# Apollo_Main_Board.net
KiCad netlist of a schematic drawn in Altium Designer
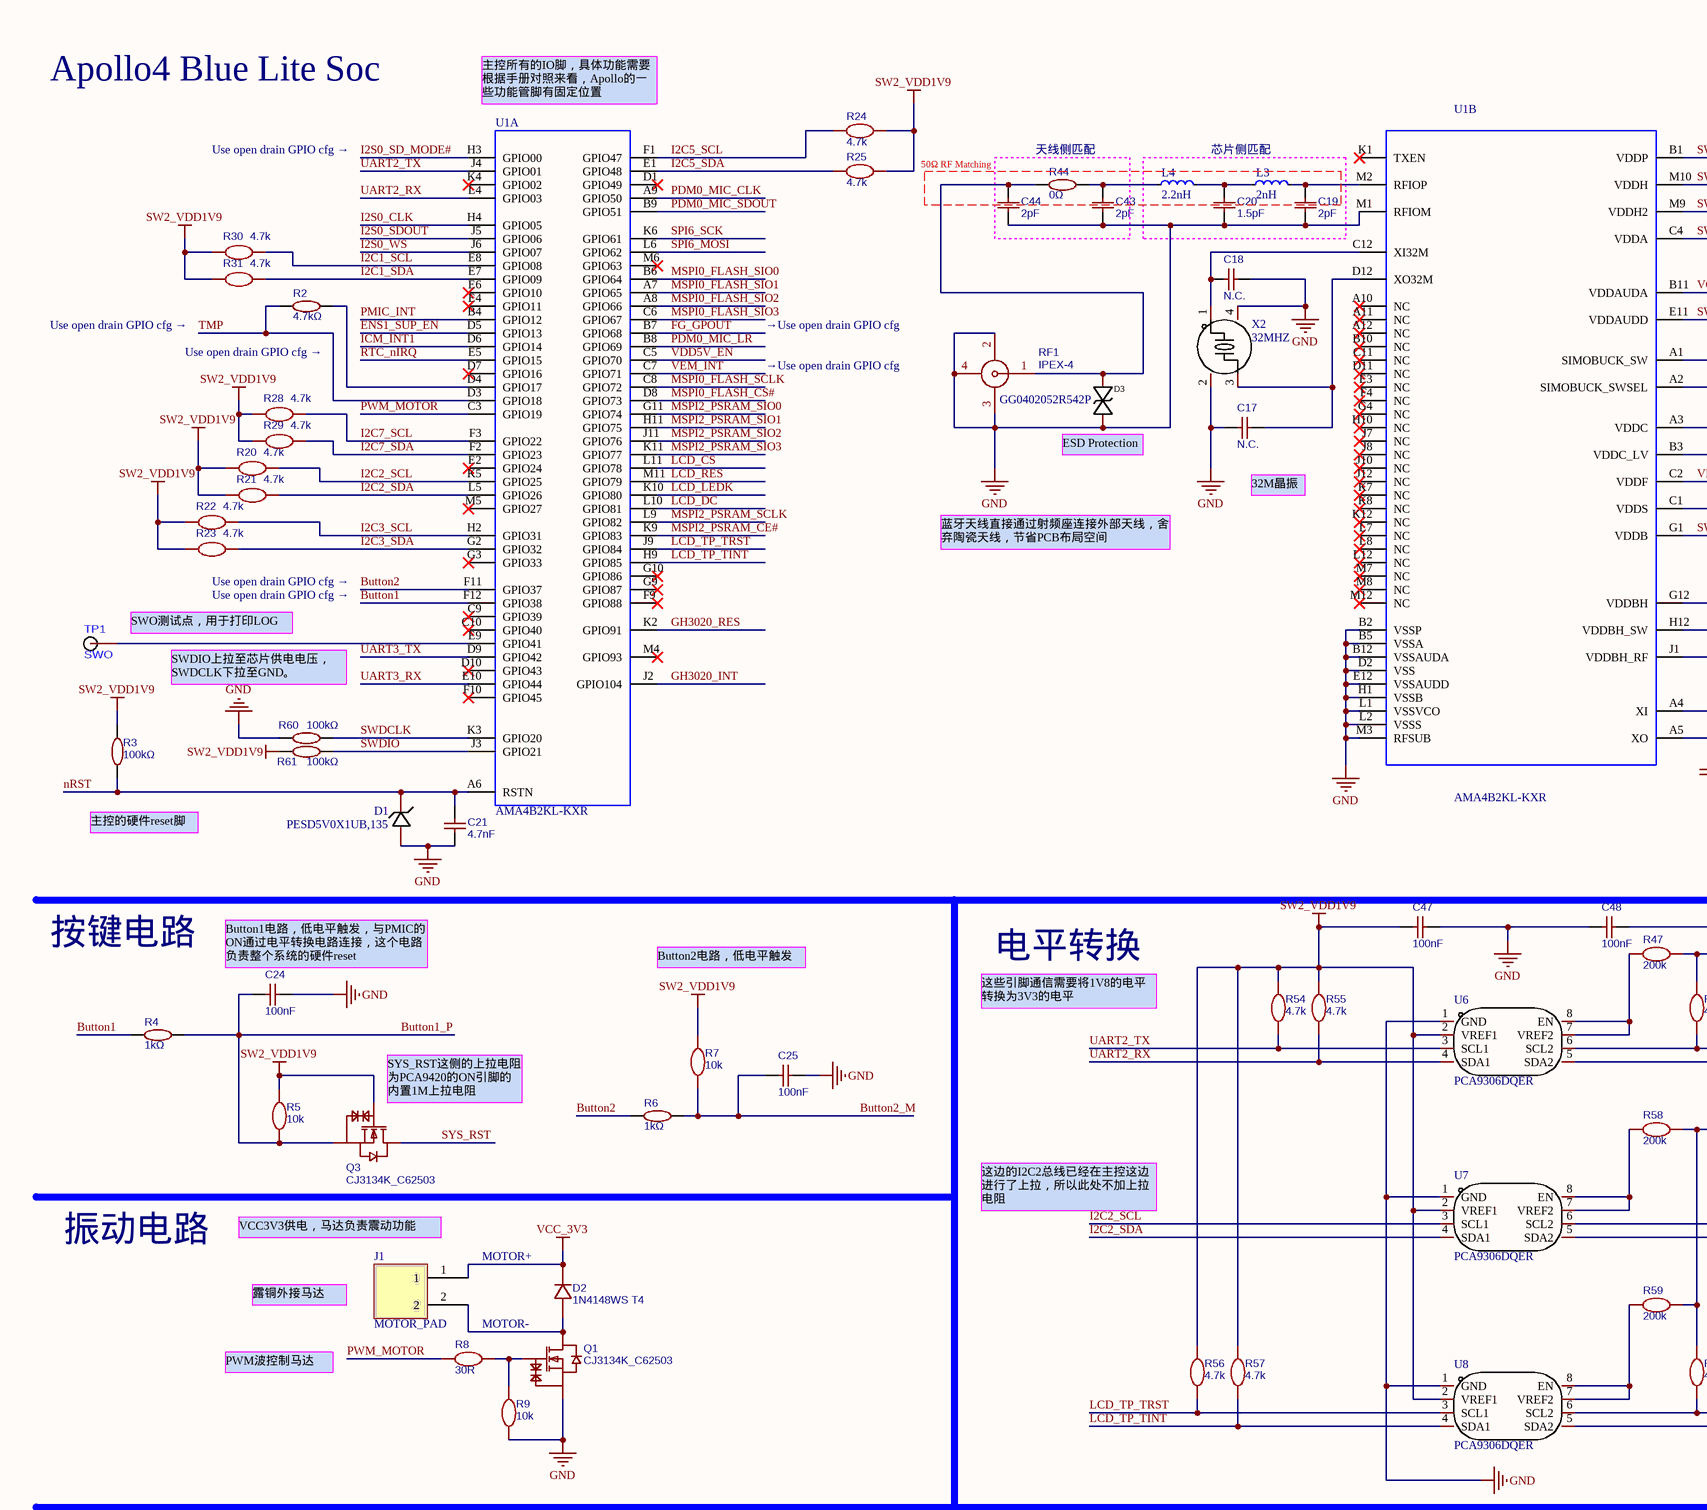
[diagram p0: Apollo_Main_Board.SchDoc, top left]
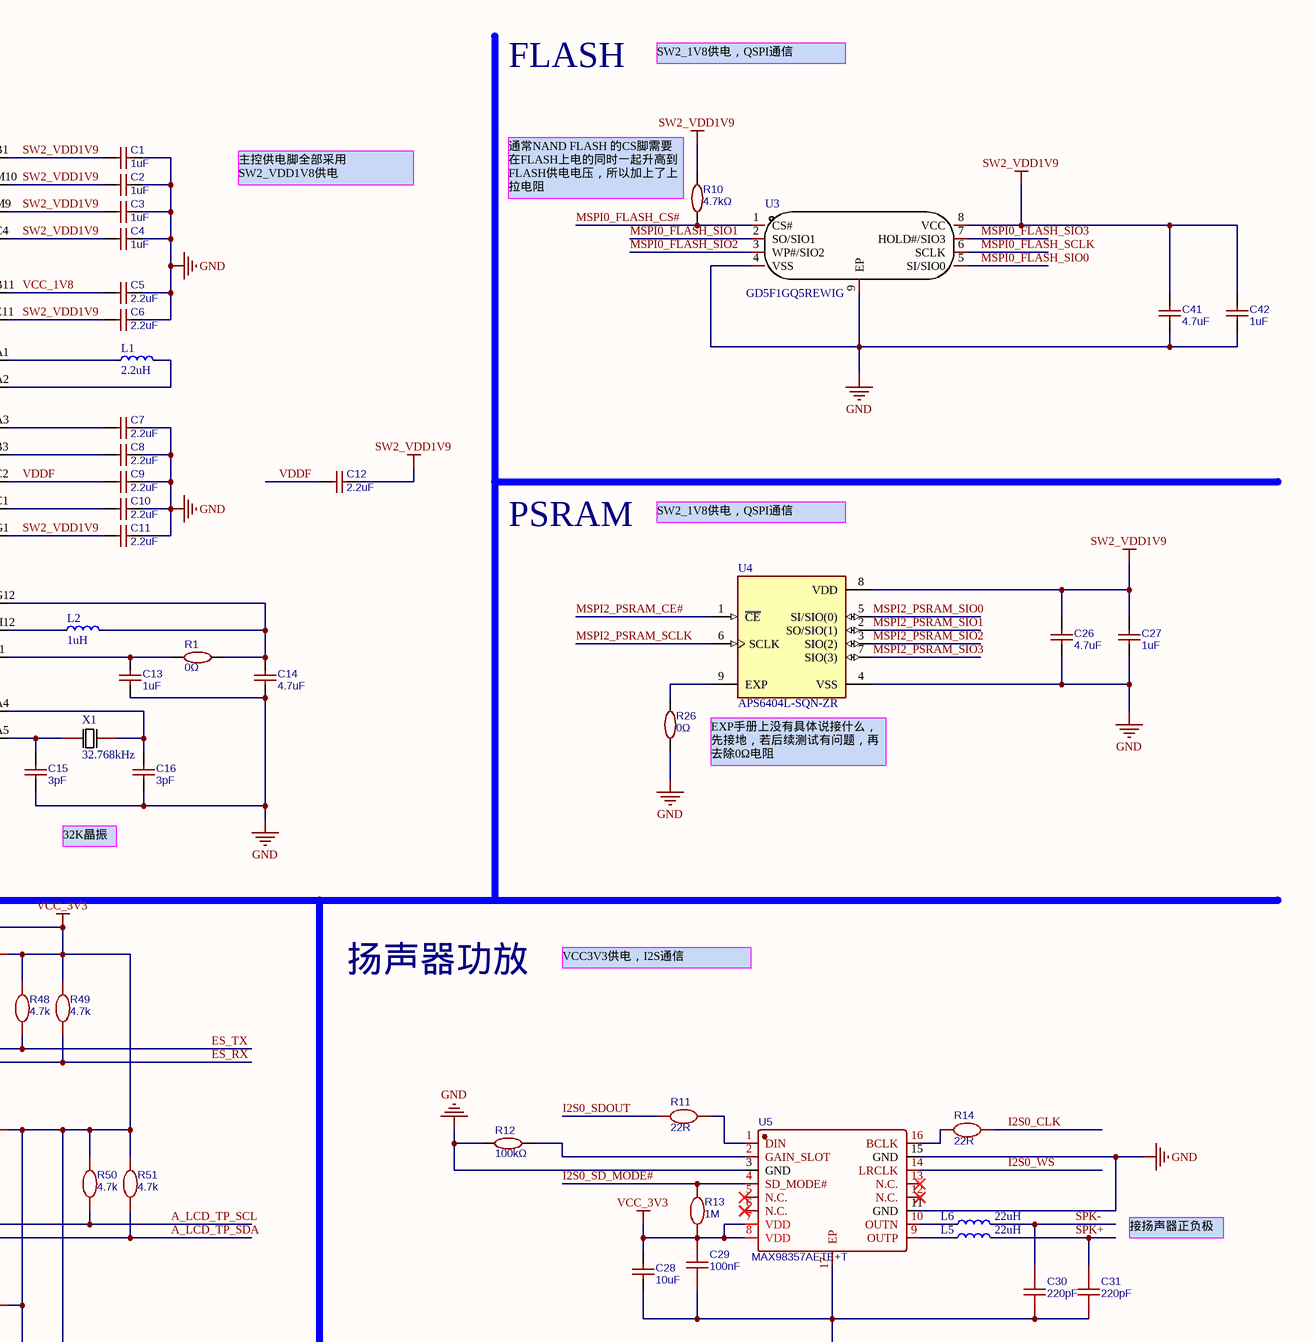
[diagram p1: Apollo_Main_Board.SchDoc, top right]
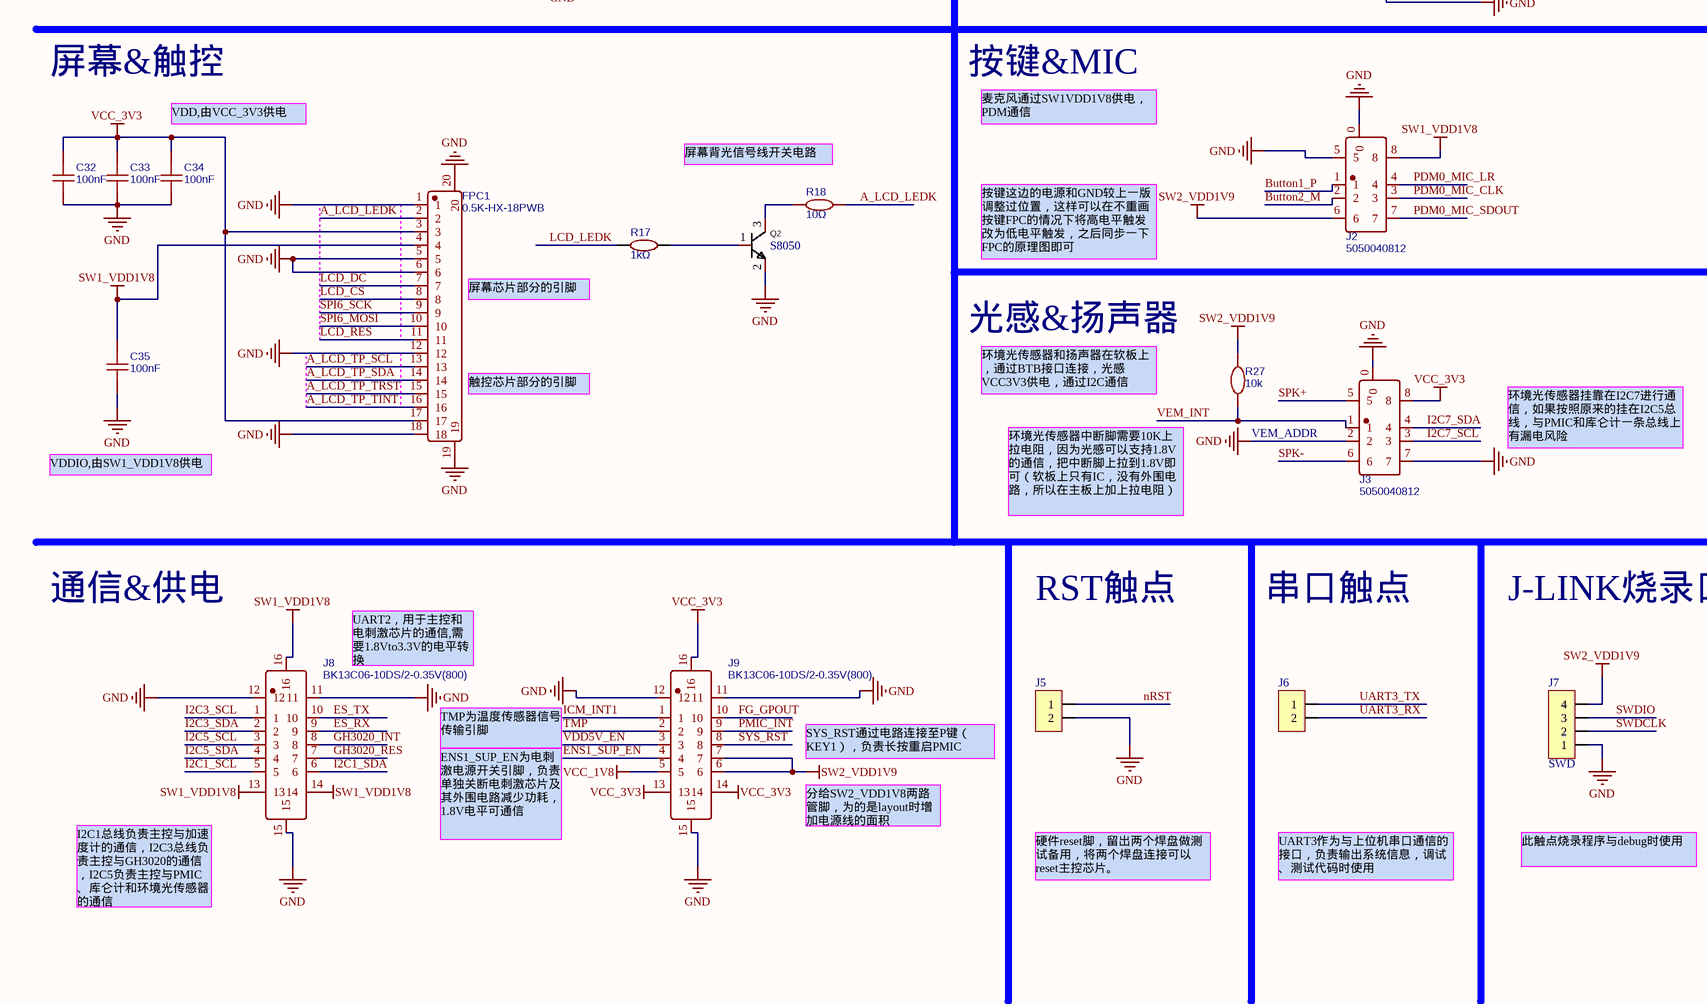
[diagram p2: Apollo_Main_Board.SchDoc, bottom left]
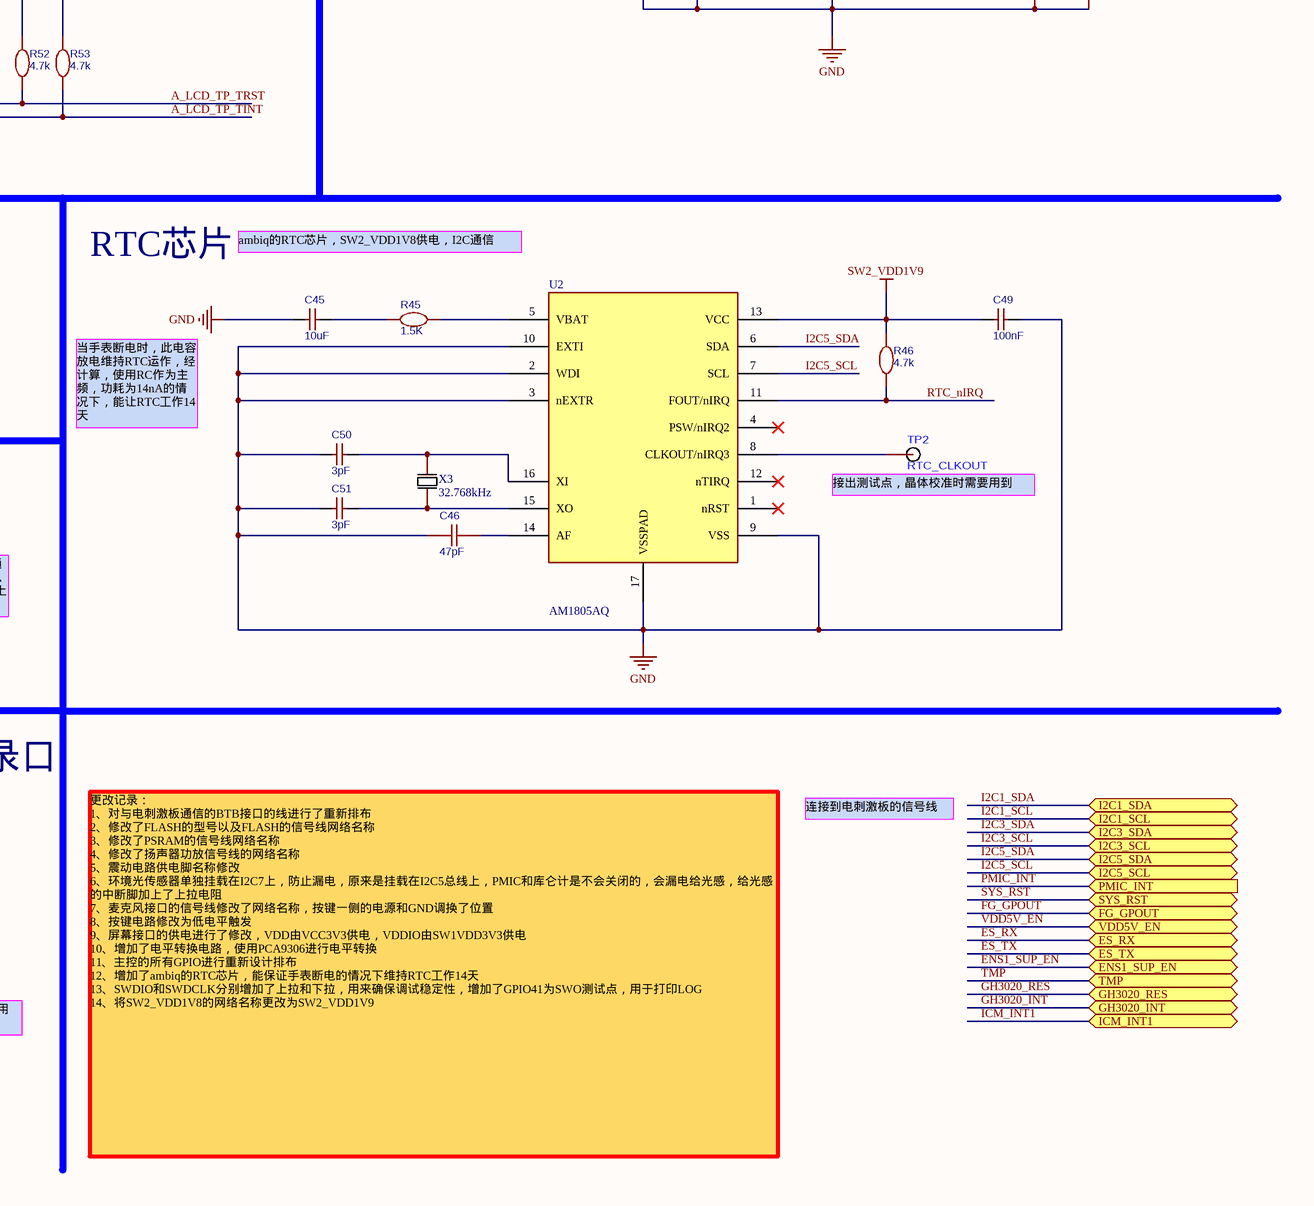
[diagram p3: Apollo_Main_Board.SchDoc, bottom right]

(export (version "E")
  (design (tool "Eeschema 10.0.6"))
  (components
    (comp (ref "C1")
      (value "1uF")
      (footprint "C0201")
      (description "GRM033R61A105ME44D\r\n精度: ±20%\r\n额定电压: 10V\r\n材质(温度系数): X5R")
      (fields
        (field (name "BOM_MANUFACTURER PART") "CL10A105KB8NNNC")
        (field (name "BOM_SUPPLIER PART") "C15849")
      )
      (libsource (lib "smart bracelet") (part "1uF"))
    )
    (comp (ref "C2")
      (value "1uF")
      (footprint "C0201")
      (description "GRM033R61A105ME44D\r\n精度: ±20%\r\n额定电压: 10V\r\n材质(温度系数): X5R")
      (fields
        (field (name "BOM_MANUFACTURER PART") "CL10A105KB8NNNC")
        (field (name "BOM_SUPPLIER PART") "C15849")
      )
      (libsource (lib "smart bracelet") (part "1uF"))
    )
    (comp (ref "C3")
      (value "1uF")
      (footprint "C0201")
      (description "GRM033R61A105ME44D\r\n精度: ±20%\r\n额定电压: 10V\r\n材质(温度系数): X5R")
      (fields
        (field (name "BOM_MANUFACTURER PART") "CL10A105KB8NNNC")
        (field (name "BOM_SUPPLIER PART") "C15849")
      )
      (libsource (lib "smart bracelet") (part "1uF"))
    )
    (comp (ref "C4")
      (value "1uF")
      (footprint "C0201")
      (description "GRM033R61A105ME44D\r\n精度: ±20%\r\n额定电压: 10V\r\n材质(温度系数): X5R")
      (fields
        (field (name "BOM_MANUFACTURER PART") "CL10A105KB8NNNC")
        (field (name "BOM_SUPPLIER PART") "C15849")
      )
      (libsource (lib "smart bracelet") (part "1uF"))
    )
    (comp (ref "C5")
      (value "2.2uF")
      (footprint "C0201")
      (description "GRM033R61A225KE47D\r\n精度: ±10%\r\n额定电压: 10V\r\n材质(温度系数): X5R")
      (fields
        (field (name "BOM_MANUFACTURER PART") "CL10A105KB8NNNC")
        (field (name "BOM_SUPPLIER PART") "C15849")
      )
      (libsource (lib "smart bracelet") (part "1uF"))
    )
    (comp (ref "C6")
      (value "2.2uF")
      (footprint "C0201")
      (description "GRM033R61A225KE47D\r\n精度: ±10%\r\n额定电压: 10V\r\n材质(温度系数): X5R")
      (fields
        (field (name "BOM_MANUFACTURER PART") "CL10A105KB8NNNC")
        (field (name "BOM_SUPPLIER PART") "C15849")
      )
      (libsource (lib "smart bracelet") (part "1uF"))
    )
    (comp (ref "C7")
      (value "2.2uF")
      (footprint "C0201")
      (description "GRM033R61A225KE47D\r\n精度: ±10%\r\n额定电压: 10V\r\n材质(温度系数): X5R")
      (fields
        (field (name "BOM_MANUFACTURER PART") "CL10A105KB8NNNC")
        (field (name "BOM_SUPPLIER PART") "C15849")
      )
      (libsource (lib "smart bracelet") (part "1uF"))
    )
    (comp (ref "C8")
      (value "2.2uF")
      (footprint "C0201")
      (description "GRM033R61A225KE47D\r\n精度: ±10%\r\n额定电压: 10V\r\n材质(温度系数): X5R")
      (fields
        (field (name "BOM_MANUFACTURER PART") "CL10A105KB8NNNC")
        (field (name "BOM_SUPPLIER PART") "C15849")
      )
      (libsource (lib "smart bracelet") (part "1uF"))
    )
    (comp (ref "C9")
      (value "2.2uF")
      (footprint "C0201")
      (description "GRM033R61A225KE47D\r\n精度: ±10%\r\n额定电压: 10V\r\n材质(温度系数): X5R")
      (fields
        (field (name "BOM_MANUFACTURER PART") "CL10A105KB8NNNC")
        (field (name "BOM_SUPPLIER PART") "C15849")
      )
      (libsource (lib "smart bracelet") (part "1uF"))
    )
    (comp (ref "C10")
      (value "2.2uF")
      (footprint "C0201")
      (description "GRM033R61A225KE47D\r\n精度: ±10%\r\n额定电压: 10V\r\n材质(温度系数): X5R")
      (fields
        (field (name "BOM_MANUFACTURER PART") "CL10A105KB8NNNC")
        (field (name "BOM_SUPPLIER PART") "C15849")
      )
      (libsource (lib "smart bracelet") (part "1uF"))
    )
    (comp (ref "C11")
      (value "2.2uF")
      (footprint "C0201")
      (description "GRM033R61A225KE47D\r\n精度: ±10%\r\n额定电压: 10V\r\n材质(温度系数): X5R")
      (fields
        (field (name "BOM_MANUFACTURER PART") "CL10A105KB8NNNC")
        (field (name "BOM_SUPPLIER PART") "C15849")
      )
      (libsource (lib "smart bracelet") (part "1uF"))
    )
    (comp (ref "C12")
      (value "2.2uF")
      (footprint "C0201")
      (description "GRM033R61A225KE47D\r\n精度: ±10%\r\n额定电压: 10V\r\n材质(温度系数): X5R")
      (fields
        (field (name "BOM_MANUFACTURER PART") "CL10A105KB8NNNC")
        (field (name "BOM_SUPPLIER PART") "C15849")
      )
      (libsource (lib "smart bracelet") (part "1uF"))
    )
    (comp (ref "C13")
      (value "1uF")
      (footprint "C0201")
      (description "GRM033R61A105ME44D\r\n精度: ±20%\r\n额定电压: 10V\r\n材质(温度系数): X5R")
      (fields
        (field (name "BOM_MANUFACTURER PART") "CL10A105KB8NNNC")
        (field (name "BOM_SUPPLIER PART") "C15849")
      )
      (libsource (lib "smart bracelet") (part "1uF"))
    )
    (comp (ref "C14")
      (value "4.7uF")
      (footprint "C0201")
      (description "GRM035R60J475ME15D\r\n精度: ±20%\r\n额定电压: 6.3V\r\n材质(温度系数): X5R")
      (fields
        (field (name "BOM_MANUFACTURER PART") "CL10A105KB8NNNC")
        (field (name "BOM_SUPPLIER PART") "C15849")
      )
      (libsource (lib "smart bracelet") (part "1uF"))
    )
    (comp (ref "C15")
      (value "3pF")
      (footprint "C0201")
      (fields
        (field (name "BOM_MANUFACTURER PART") "CL10A105KB8NNNC")
        (field (name "BOM_SUPPLIER PART") "C15849")
      )
      (libsource (lib "smart bracelet") (part "1uF"))
    )
    (comp (ref "C16")
      (value "3pF")
      (footprint "C0201")
      (fields
        (field (name "BOM_MANUFACTURER PART") "CL10A105KB8NNNC")
        (field (name "BOM_SUPPLIER PART") "C15849")
      )
      (libsource (lib "smart bracelet") (part "1uF"))
    )
    (comp (ref "C17")
      (value "N.C.")
      (footprint "C0201")
      (description "现在选的32MHZ晶振内部负载电容8pF，可以不需要外部电容，所以NC，只留焊盘，不用焊接")
      (fields
        (field (name "BOM_MANUFACTURER PART") "CL10A105KB8NNNC")
        (field (name "BOM_SUPPLIER PART") "C15849")
      )
      (libsource (lib "smart bracelet") (part "1uF"))
    )
    (comp (ref "C18")
      (value "N.C.")
      (footprint "C0201")
      (description "现在选的32MHZ晶振内部负载电容8pF，可以不需要外部电容，所以NC，只留焊盘，不用焊接")
      (fields
        (field (name "BOM_MANUFACTURER PART") "CL10A105KB8NNNC")
        (field (name "BOM_SUPPLIER PART") "C15849")
      )
      (libsource (lib "smart bracelet") (part "1uF"))
    )
    (comp (ref "C19")
      (value "2pF")
      (footprint "C0201")
      (description "GRM0335C1H2R0BA01D\r\n精度: ±0.1pF\r\n额定电压: 50V\r\n材质(温度系数): C0G")
      (fields
        (field (name "BOM_MANUFACTURER PART") "CL10A105KB8NNNC")
        (field (name "BOM_SUPPLIER PART") "C15849")
      )
      (libsource (lib "smart bracelet") (part "1uF"))
    )
    (comp (ref "C20")
      (value "1.5pF")
      (footprint "C0201")
      (description "GRM0335C1H1R5BA01D\r\n精度: ±0.1pF\r\n额定电压: 50V\r\n材质(温度系数): C0G")
      (fields
        (field (name "BOM_MANUFACTURER PART") "CL10A105KB8NNNC")
        (field (name "BOM_SUPPLIER PART") "C15849")
      )
      (libsource (lib "smart bracelet") (part "1uF"))
    )
    (comp (ref "C21")
      (value "4.7nF")
      (footprint "C0201")
      (description "CC0201KRX7R8BB472\r\n精度: ±10%\r\n额定电压: 25V\r\n材质(温度系数): X7R")
      (fields
        (field (name "BOM_MANUFACTURER PART") "CL10A105KB8NNNC")
        (field (name "BOM_SUPPLIER PART") "C15849")
      )
      (libsource (lib "smart bracelet") (part "1uF"))
    )
    (comp (ref "C24")
      (value "100nF")
      (footprint "C0201")
      (description "CL03A104KO3NNNC\r\n精度: ±10%\r\n额定电压: 16V\r\n材质(温度系数): X5R")
      (fields
        (field (name "BOM_MANUFACTURER PART") "CL10A105KB8NNNC")
        (field (name "BOM_SUPPLIER PART") "C15849")
      )
      (libsource (lib "smart bracelet") (part "1uF"))
    )
    (comp (ref "C25")
      (value "100nF")
      (footprint "C0201")
      (description "CL03A104KO3NNNC\r\n精度: ±10%\r\n额定电压: 16V\r\n材质(温度系数): X5R")
      (fields
        (field (name "BOM_MANUFACTURER PART") "CL10A105KB8NNNC")
        (field (name "BOM_SUPPLIER PART") "C15849")
      )
      (libsource (lib "smart bracelet") (part "1uF"))
    )
    (comp (ref "C26")
      (value "4.7uF")
      (footprint "C0201")
      (description "GRM035R60J475ME15D\r\n精度: ±20%\r\n额定电压: 6.3V\r\n材质(温度系数): X5R")
      (fields
        (field (name "BOM_MANUFACTURER PART") "CL10A105KB8NNNC")
        (field (name "BOM_SUPPLIER PART") "C15849")
      )
      (libsource (lib "smart bracelet") (part "1uF"))
    )
    (comp (ref "C27")
      (value "1uF")
      (footprint "C0201")
      (description "GRM033R61A105ME44D\r\n精度: ±20%\r\n额定电压: 10V\r\n材质(温度系数): X5R")
      (fields
        (field (name "BOM_MANUFACTURER PART") "CL10A105KB8NNNC")
        (field (name "BOM_SUPPLIER PART") "C15849")
      )
      (libsource (lib "smart bracelet") (part "1uF"))
    )
    (comp (ref "C28")
      (value "10uF")
      (footprint "C0402")
      (description "GRM155R61A106ME11D\r\n精度: ±20%\r\n额定电压: 10V\r\n材质(温度系数): X5R")
      (fields
        (field (name "BOM_MANUFACTURER PART") "CL10A105KB8NNNC")
        (field (name "BOM_SUPPLIER PART") "C15849")
      )
      (libsource (lib "smart bracelet") (part "1uF"))
    )
    (comp (ref "C29")
      (value "100nF")
      (footprint "smart bracelet:C0201")
      (description "CL03A104KO3NNNC\r\n额定电压: 16V\r\n材质(温度系数): X5R")
      (fields
        (field (name "BOM_MANUFACTURER PART") "CL10B104KB8NNNC")
        (field (name "BOM_SUPPLIER PART") "C1591")
      )
      (libsource (lib "smart bracelet") (part "100nF"))
    )
    (comp (ref "C30")
      (value "220pF")
      (footprint "smart bracelet:C0201")
      (description "GRM0335C1H221JA01D\r\n精度: ±5%\r\n额定电压: 50V\r\n材质(温度系数): C0G")
      (fields
        (field (name "BOM_SUPPLIER PART") "C913904")
        (field (name "BOM_MANUFACTURER PART") "CL10A225KB8NNNC")
        (field (name "CONTRIBUTOR") "LCSC")
      )
      (libsource (lib "smart bracelet") (part "C0201"))
    )
    (comp (ref "C31")
      (value "220pF")
      (footprint "smart bracelet:C0201")
      (description "GRM0335C1H221JA01D\r\n精度: ±5%\r\n额定电压: 50V\r\n材质(温度系数): C0G")
      (fields
        (field (name "BOM_SUPPLIER PART") "C913904")
        (field (name "BOM_MANUFACTURER PART") "CL10A225KB8NNNC")
        (field (name "CONTRIBUTOR") "LCSC")
      )
      (libsource (lib "smart bracelet") (part "C0201"))
    )
    (comp (ref "C32")
      (value "100nF")
      (footprint "smart bracelet:C0201")
      (description "CL03A104KO3NNNC\r\n额定电压: 16V\r\n材质(温度系数): X5R")
      (fields
        (field (name "BOM_MANUFACTURER PART") "CL10B104KB8NNNC")
        (field (name "BOM_SUPPLIER PART") "C1591")
      )
      (libsource (lib "smart bracelet") (part "100nF"))
    )
    (comp (ref "C33")
      (value "100nF")
      (footprint "smart bracelet:C0201")
      (description "CL03A104KO3NNNC\r\n额定电压: 16V\r\n材质(温度系数): X5R")
      (fields
        (field (name "BOM_MANUFACTURER PART") "CL10B104KB8NNNC")
        (field (name "BOM_SUPPLIER PART") "C1591")
      )
      (libsource (lib "smart bracelet") (part "100nF"))
    )
    (comp (ref "C34")
      (value "100nF")
      (footprint "smart bracelet:C0201")
      (description "CL03A104KO3NNNC\r\n额定电压: 16V\r\n材质(温度系数): X5R")
      (fields
        (field (name "BOM_MANUFACTURER PART") "CL10B104KB8NNNC")
        (field (name "BOM_SUPPLIER PART") "C1591")
      )
      (libsource (lib "smart bracelet") (part "100nF"))
    )
    (comp (ref "C35")
      (value "100nF")
      (footprint "smart bracelet:C0201")
      (description "CL03A104KO3NNNC\r\n额定电压: 16V\r\n材质(温度系数): X5R")
      (fields
        (field (name "BOM_MANUFACTURER PART") "CL10B104KB8NNNC")
        (field (name "BOM_SUPPLIER PART") "C1591")
      )
      (libsource (lib "smart bracelet") (part "100nF"))
    )
    (comp (ref "C41")
      (value "4.7uF")
      (footprint "C0201")
      (description "GRM035R60J475ME15D\r\n精度: ±20%\r\n额定电压: 6.3V\r\n材质(温度系数): X5R")
      (fields
        (field (name "BOM_MANUFACTURER PART") "CL10A105KB8NNNC")
        (field (name "BOM_SUPPLIER PART") "C15849")
      )
      (libsource (lib "smart bracelet") (part "1uF"))
    )
    (comp (ref "C42")
      (value "1uF")
      (footprint "C0201")
      (description "GRM033R61A105ME44D\r\n精度: ±20%\r\n额定电压: 10V\r\n材质(温度系数): X5R")
      (fields
        (field (name "BOM_MANUFACTURER PART") "CL10A105KB8NNNC")
        (field (name "BOM_SUPPLIER PART") "C15849")
      )
      (libsource (lib "smart bracelet") (part "1uF"))
    )
    (comp (ref "C43")
      (value "2pF")
      (footprint "C0201")
      (description "GRM0335C1H2R0BA01D\r\n精度: ±0.1pF\r\n额定电压: 50V\r\n材质(温度系数): C0G")
      (fields
        (field (name "BOM_MANUFACTURER PART") "CL10A105KB8NNNC")
        (field (name "BOM_SUPPLIER PART") "C15849")
      )
      (libsource (lib "smart bracelet") (part "1uF"))
    )
    (comp (ref "C44")
      (value "2pF")
      (footprint "C0201")
      (description "GRM0335C1H2R0BA01D\r\n精度: ±0.1pF\r\n额定电压: 50V\r\n材质(温度系数): C0G")
      (fields
        (field (name "BOM_MANUFACTURER PART") "CL10A105KB8NNNC")
        (field (name "BOM_SUPPLIER PART") "C15849")
      )
      (libsource (lib "smart bracelet") (part "1uF"))
    )
    (comp (ref "C45")
      (value "10uF")
      (footprint "C0402")
      (description "GRM155R61A106ME11D\r\n精度: ±20%\r\n额定电压: 10V\r\n材质(温度系数): X5R")
      (fields
        (field (name "BOM_MANUFACTURER PART") "CL10A105KB8NNNC")
        (field (name "BOM_SUPPLIER PART") "C15849")
      )
      (libsource (lib "smart bracelet") (part "1uF"))
    )
    (comp (ref "C46")
      (value "47pF")
      (footprint "smart bracelet:C0201")
      (fields
        (field (name "BOM_SUPPLIER PART") "C913904")
        (field (name "BOM_MANUFACTURER PART") "CL10A225KB8NNNC")
        (field (name "CONTRIBUTOR") "LCSC")
      )
      (libsource (lib "smart bracelet") (part "C0201"))
    )
    (comp (ref "C47")
      (value "100nF")
      (footprint "C0201")
      (description "CL03A104KO3NNNC\r\n精度: ±10%\r\n额定电压: 16V\r\n材质(温度系数): X5R")
      (fields
        (field (name "BOM_MANUFACTURER PART") "CL10A105KB8NNNC")
        (field (name "BOM_SUPPLIER PART") "C15849")
      )
      (libsource (lib "smart bracelet") (part "1uF"))
    )
    (comp (ref "C48")
      (value "100nF")
      (footprint "C0201")
      (description "CL03A104KO3NNNC\r\n精度: ±10%\r\n额定电压: 16V\r\n材质(温度系数): X5R")
      (fields
        (field (name "BOM_MANUFACTURER PART") "CL10A105KB8NNNC")
        (field (name "BOM_SUPPLIER PART") "C15849")
      )
      (libsource (lib "smart bracelet") (part "1uF"))
    )
    (comp (ref "C49")
      (value "100nF")
      (footprint "C0201")
      (description "CL03A104KO3NNNC\r\n精度: ±10%\r\n额定电压: 16V\r\n材质(温度系数): X5R")
      (fields
        (field (name "BOM_MANUFACTURER PART") "CL10A105KB8NNNC")
        (field (name "BOM_SUPPLIER PART") "C15849")
      )
      (libsource (lib "smart bracelet") (part "1uF"))
    )
    (comp (ref "C50")
      (value "3pF")
      (footprint "C0201")
      (fields
        (field (name "BOM_MANUFACTURER PART") "CL10A105KB8NNNC")
        (field (name "BOM_SUPPLIER PART") "C15849")
      )
      (libsource (lib "smart bracelet") (part "1uF"))
    )
    (comp (ref "C51")
      (value "3pF")
      (footprint "C0201")
      (fields
        (field (name "BOM_MANUFACTURER PART") "CL10A105KB8NNNC")
        (field (name "BOM_SUPPLIER PART") "C15849")
      )
      (libsource (lib "smart bracelet") (part "1uF"))
    )
    (comp (ref "D1")
      (value "PESD5V0X1UB,135")
      (footprint "SOD-523_L1.2-W0.8-LS1.6-RD")
      (fields (field (name "MANUFACTURER") "Nexperia(安世)") (field (name "NAME") "PESD5V0X1UB,135"))
      (libsource (lib "smart bracelet") (part "PESD5V0X1UB,135"))
    )
    (comp (ref "D2")
      (value "1N4148WS T4")
      (footprint "smart bracelet:SOD-323_L1.8-W1.3-LS2.5-RD")
      (fields (field (name "MANUFACTURER") "CJ(江苏长电/长晶)") (field (name "MANUFACTURER PART") "1N4148WS"))
      (libsource (lib "smart bracelet") (part "1N4148WS T4"))
    )
    (comp (ref "D3")
      (value "GG0402052R542P")
      (footprint "smart bracelet:0402")
      (fields (field (name "MANUFACTURER") "Kyocera AVX"))
      (libsource (lib "smart bracelet") (part "GG0402052R542P"))
    )
    (comp (ref "FPC1")
      (value "0.5K-HX-18PWB")
      (footprint "smart bracelet:FPC-SMD_18P-P0.50_HDGC_0.5K-HX-18PWB")
      (fields (field (name "BOM_SUPPLIER PART") "C2919497") (field (name "CONTRIBUTOR") "LCSC"))
      (libsource (lib "smart bracelet") (part "0.5K-HX-18PWB"))
    )
    (comp (ref "J1")
      (value "MOTOR_PAD")
      (footprint "smart bracelet:MOTOR_PAD")
      (libsource (lib "smart bracelet") (part "MOTOR_PAD"))
    )
    (comp (ref "J2")
      (value "5050040812")
      (footprint "smart bracelet:CONN-SMD_4P-P0.40_5050040812")
      (fields (field (name "MANUFACTURER") "MOLEX") (field (name "CONTRIBUTOR") "lcsc"))
      (libsource (lib "smart bracelet") (part "5050040812_8pin_ds"))
    )
    (comp (ref "J3")
      (value "5050040812")
      (footprint "smart bracelet:CONN-SMD_4P-P0.40_5050040812")
      (fields (field (name "MANUFACTURER") "MOLEX") (field (name "CONTRIBUTOR") "lcsc"))
      (libsource (lib "smart bracelet") (part "5050040812_8pin_ds"))
    )
    (comp (ref "J5")
      (value "~")
      (footprint "2PIN_1.27mm")
      (description "Header, 2-Pin, encryption interface")
      (fields (field (name "PUBLISHER") "Altium Limited"))
      (libsource (lib "smart bracelet") (part "Header 2"))
    )
    (comp (ref "J6")
      (value "~")
      (footprint "2PIN_1.27mm")
      (description "Header, 2-Pin, encryption interface")
      (fields (field (name "PUBLISHER") "Altium Limited"))
      (libsource (lib "smart bracelet") (part "Header 2"))
    )
    (comp (ref "J7")
      (value "SWD")
      (footprint "4PIN_1.27mm")
      (description "Header, 4-Pin")
      (fields (field (name "PUBLISHER") "Altium Limited"))
      (libsource (lib "smart bracelet") (part "Header 4"))
    )
    (comp (ref "J8")
      (value "BK13C06-10DS/2-0.35V(800)")
      (footprint "smart bracelet:CONN-SMD_BK13C06-10DS-2-0.35V-800")
      (fields (field (name "MANUFACTURER") "HRS(广濑)") (field (name "CONTRIBUTOR") "lcsc"))
      (libsource (lib "smart bracelet") (part "10pin_ds_BK13C06-10DS/2-0.35V(800)"))
    )
    (comp (ref "J9")
      (value "BK13C06-10DS/2-0.35V(800)")
      (footprint "smart bracelet:CONN-SMD_BK13C06-10DS-2-0.35V-800")
      (fields (field (name "MANUFACTURER") "HRS(广濑)") (field (name "CONTRIBUTOR") "lcsc"))
      (libsource (lib "smart bracelet") (part "10pin_ds_BK13C06-10DS/2-0.35V(800)"))
    )
    (comp (ref "L1")
      (value "2.2uH")
      (footprint "C0603")
      (description "MAP1608ST2R2MMPK（这是按照官方推荐的选型，不要轻易变动）")
      (fields (field (name "PART NUMBER") "L0603-10µ"))
      (libsource (lib "smart bracelet") (part "10uH"))
    )
    (comp (ref "L2")
      (value "1uH")
      (footprint "C0603")
      (description "MAP1608ST1R0MMPK（这是按照官方推荐的选型，不要轻易变动）")
      (fields (field (name "PART NUMBER") "L0603-10µ"))
      (libsource (lib "smart bracelet") (part "10uH"))
    )
    (comp (ref "L3")
      (value "2nH")
      (footprint "C0201")
      (fields (field (name "PART NUMBER") "L0603-10µ"))
      (libsource (lib "smart bracelet") (part "10uH"))
    )
    (comp (ref "L4")
      (value "2.2nH")
      (footprint "C0201")
      (fields (field (name "PART NUMBER") "L0603-10µ"))
      (libsource (lib "smart bracelet") (part "10uH"))
    )
    (comp (ref "L5")
      (value "22uH")
      (footprint "0603A")
      (fields (field (name "PART NUMBER") "L0603-10µ"))
      (libsource (lib "smart bracelet") (part "10uH"))
    )
    (comp (ref "L6")
      (value "22uH")
      (footprint "0603A")
      (fields (field (name "PART NUMBER") "L0603-10µ"))
      (libsource (lib "smart bracelet") (part "10uH"))
    )
    (comp (ref "Q1")
      (value "CJ3134K_C62503")
      (footprint "smart bracelet:SOT-723_L1.2-W0.8-P0.40-LS1.2-BR")
      (fields (field (name "MANUFACTURER") "CJ(江苏长电/长晶)") (field (name "MANUFACTURER PART") "CJ3134K KF"))
      (libsource (lib "smart bracelet") (part "CJ3134K_C62503"))
    )
    (comp (ref "Q2")
      (value "S8050")
      (footprint "smart bracelet:SOT-23")
      (fields (field (name "MANUFACTURER") "星海"))
      (libsource (lib "smart bracelet") (part "S8050"))
    )
    (comp (ref "Q3")
      (value "CJ3134K_C62503")
      (footprint "smart bracelet:SOT-723_L1.2-W0.8-P0.40-LS1.2-BR")
      (fields (field (name "MANUFACTURER") "CJ(江苏长电/长晶)") (field (name "MANUFACTURER PART") "CJ3134K KF"))
      (libsource (lib "smart bracelet") (part "CJ3134K_C62503"))
    )
    (comp (ref "R1")
      (value "0Ω")
      (footprint "smart bracelet:RES0201")
      (description "RC0201FR-070RL\r\n品牌: YAGEO(国巨)\r\n封装: 0201\r\n电阻类型: 厚膜电阻\r\n阻值: 0Ω\r\n精度: ±1%\r\n功率: 50mW")
      (fields
        (field (name "BOM_MANUFACTURER PART") "ERJ3GEY0R00V")
        (field (name "BOM_SUPPLIER PART") "C122704")
      )
      (libsource (lib "smart bracelet") (part "0Ω"))
    )
    (comp (ref "R2")
      (value "4.7kΩ")
      (footprint "smart bracelet:RES0201")
      (description "0201WMF4701TEE\r\n精度: ±1%\r\n功率: 50mW")
      (fields
        (field (name "BOM_MANUFACTURER PART") "ERJ3GEY0R00V")
        (field (name "BOM_SUPPLIER PART") "C122704")
      )
      (libsource (lib "smart bracelet") (part "0Ω"))
    )
    (comp (ref "R3")
      (value "100kΩ")
      (footprint "smart bracelet:RES0201")
      (description "0201WMF1003TEE\r\n精度: ±1%\r\n功率: 50mW")
      (fields
        (field (name "BOM_MANUFACTURER PART") "ERJ3GEY0R00V")
        (field (name "BOM_SUPPLIER PART") "C122704")
      )
      (libsource (lib "smart bracelet") (part "0Ω"))
    )
    (comp (ref "R4")
      (value "1kΩ")
      (footprint "smart bracelet:RES0201")
      (description "0201WMF1001TEE\r\n精度: ±1%\r\n功率: 50mW")
      (fields
        (field (name "BOM_MANUFACTURER PART") "ERJ3GEY0R00V")
        (field (name "BOM_SUPPLIER PART") "C122704")
      )
      (libsource (lib "smart bracelet") (part "0Ω"))
    )
    (comp (ref "R5")
      (value "10k")
      (footprint "smart bracelet:RES0201")
      (description "0201WMF1002TEE\r\n精度: ±1%\r\n功率: 50mW")
      (fields
        (field (name "BOM_SUPPLIER PART") "C2989113")
        (field (name "BOM_MANUFACTURER PART") "TC0325B1000T5F")
        (field (name "CONTRIBUTOR") "lcsc")
      )
      (libsource (lib "smart bracelet") (part "RES0201"))
    )
    (comp (ref "R6")
      (value "1kΩ")
      (footprint "smart bracelet:RES0201")
      (description "0201WMF1001TEE\r\n精度: ±1%\r\n功率: 50mW")
      (fields
        (field (name "BOM_MANUFACTURER PART") "ERJ3GEY0R00V")
        (field (name "BOM_SUPPLIER PART") "C122704")
      )
      (libsource (lib "smart bracelet") (part "0Ω"))
    )
    (comp (ref "R7")
      (value "10k")
      (footprint "smart bracelet:RES0201")
      (description "0201WMF1002TEE\r\n精度: ±1%\r\n功率: 50mW")
      (fields
        (field (name "BOM_SUPPLIER PART") "C2989113")
        (field (name "BOM_MANUFACTURER PART") "TC0325B1000T5F")
        (field (name "CONTRIBUTOR") "lcsc")
      )
      (libsource (lib "smart bracelet") (part "RES0201"))
    )
    (comp (ref "R8")
      (value "30R")
      (footprint "smart bracelet:RES0201")
      (description "RC-01W30R0FT\r\n精度: ±1%\r\n功率: 50mW")
      (fields
        (field (name "BOM_SUPPLIER PART") "C2989113")
        (field (name "BOM_MANUFACTURER PART") "TC0325B1000T5F")
        (field (name "CONTRIBUTOR") "lcsc")
      )
      (libsource (lib "smart bracelet") (part "RES0201"))
    )
    (comp (ref "R9")
      (value "10k")
      (footprint "smart bracelet:RES0201")
      (description "0201WMF1002TEE\r\n精度: ±1%\r\n功率: 50mW")
      (fields
        (field (name "BOM_SUPPLIER PART") "C2989113")
        (field (name "BOM_MANUFACTURER PART") "TC0325B1000T5F")
        (field (name "CONTRIBUTOR") "lcsc")
      )
      (libsource (lib "smart bracelet") (part "RES0201"))
    )
    (comp (ref "R10")
      (value "4.7kΩ")
      (footprint "smart bracelet:RES0201")
      (description "0201WMF4701TEE\r\n精度: ±1%\r\n功率: 50mW")
      (fields
        (field (name "BOM_MANUFACTURER PART") "ERJ3GEY0R00V")
        (field (name "BOM_SUPPLIER PART") "C122704")
      )
      (libsource (lib "smart bracelet") (part "0Ω"))
    )
    (comp (ref "R11")
      (value "22R")
      (footprint "smart bracelet:RES0201")
      (description "RC0201FR-0722RL\r\n精度: ±1%\r\n功率: 50mW")
      (fields
        (field (name "BOM_SUPPLIER PART") "C2989113")
        (field (name "BOM_MANUFACTURER PART") "TC0325B1000T5F")
        (field (name "CONTRIBUTOR") "lcsc")
      )
      (libsource (lib "smart bracelet") (part "RES0201"))
    )
    (comp (ref "R12")
      (value "100kΩ")
      (footprint "smart bracelet:RES0201")
      (description "0201WMF1003TEE\r\n精度: ±1%\r\n功率: 50mW")
      (fields
        (field (name "BOM_MANUFACTURER PART") "ERJ3GEY0R00V")
        (field (name "BOM_SUPPLIER PART") "C122704")
      )
      (libsource (lib "smart bracelet") (part "0Ω"))
    )
    (comp (ref "R13")
      (value "1M")
      (footprint "smart bracelet:RES0201")
      (description "RC0201FR-071ML\r\n精度: ±1%\r\n功率: 50mW")
      (fields
        (field (name "BOM_SUPPLIER PART") "C2989113")
        (field (name "BOM_MANUFACTURER PART") "TC0325B1000T5F")
        (field (name "CONTRIBUTOR") "lcsc")
      )
      (libsource (lib "smart bracelet") (part "RES0201"))
    )
    (comp (ref "R14")
      (value "22R")
      (footprint "smart bracelet:RES0201")
      (description "RC0201FR-0722RL\r\n精度: ±1%\r\n功率: 50mW")
      (fields
        (field (name "BOM_SUPPLIER PART") "C2989113")
        (field (name "BOM_MANUFACTURER PART") "TC0325B1000T5F")
        (field (name "CONTRIBUTOR") "lcsc")
      )
      (libsource (lib "smart bracelet") (part "RES0201"))
    )
    (comp (ref "R17")
      (value "1kΩ")
      (footprint "smart bracelet:RES0201")
      (description "0201WMF1001TEE\r\n精度: ±1%\r\n功率: 50mW")
      (fields
        (field (name "BOM_MANUFACTURER PART") "ERJ3GEY0R00V")
        (field (name "BOM_SUPPLIER PART") "C122704")
      )
      (libsource (lib "smart bracelet") (part "0Ω"))
    )
    (comp (ref "R18")
      (value "10Ω")
      (footprint "smart bracelet:RES0201")
      (description "FRC0201F10R0TS\r\n精度: ±1%\r\n功率: 50mW")
      (fields
        (field (name "BOM_SUPPLIER PART") "C441910")
        (field (name "BOM_MANUFACTURER PART") "ERJPA3F10R0V")
        (field (name "CONTRIBUTOR") "lcsc")
      )
      (libsource (lib "smart bracelet") (part "10Ω"))
    )
    (comp (ref "R20")
      (value "4.7k")
      (footprint "smart bracelet:RES0201")
      (description "0201WMF4701TEE\r\n精度: ±1%\r\n功率: 50mW")
      (fields
        (field (name "BOM_SUPPLIER PART") "C2989113")
        (field (name "BOM_MANUFACTURER PART") "TC0325B1000T5F")
        (field (name "CONTRIBUTOR") "lcsc")
      )
      (libsource (lib "smart bracelet") (part "RES0402"))
    )
    (comp (ref "R21")
      (value "4.7k")
      (footprint "smart bracelet:RES0201")
      (description "0201WMF4701TEE\r\n精度: ±1%\r\n功率: 50mW")
      (fields
        (field (name "BOM_SUPPLIER PART") "C2989113")
        (field (name "BOM_MANUFACTURER PART") "TC0325B1000T5F")
        (field (name "CONTRIBUTOR") "lcsc")
      )
      (libsource (lib "smart bracelet") (part "RES0402"))
    )
    (comp (ref "R22")
      (value "4.7k")
      (footprint "smart bracelet:RES0201")
      (description "0201WMF4701TEE\r\n精度: ±1%\r\n功率: 50mW")
      (fields
        (field (name "BOM_SUPPLIER PART") "C2989113")
        (field (name "BOM_MANUFACTURER PART") "TC0325B1000T5F")
        (field (name "CONTRIBUTOR") "lcsc")
      )
      (libsource (lib "smart bracelet") (part "RES0402"))
    )
    (comp (ref "R23")
      (value "4.7k")
      (footprint "smart bracelet:RES0201")
      (description "0201WMF4701TEE\r\n精度: ±1%\r\n功率: 50mW")
      (fields
        (field (name "BOM_SUPPLIER PART") "C2989113")
        (field (name "BOM_MANUFACTURER PART") "TC0325B1000T5F")
        (field (name "CONTRIBUTOR") "lcsc")
      )
      (libsource (lib "smart bracelet") (part "RES0402"))
    )
    (comp (ref "R24")
      (value "4.7k")
      (footprint "smart bracelet:RES0201")
      (description "0201WMF4701TEE\r\n精度: ±1%\r\n功率: 50mW")
      (fields
        (field (name "BOM_SUPPLIER PART") "C2989113")
        (field (name "BOM_MANUFACTURER PART") "TC0325B1000T5F")
        (field (name "CONTRIBUTOR") "lcsc")
      )
      (libsource (lib "smart bracelet") (part "RES0402"))
    )
    (comp (ref "R25")
      (value "4.7k")
      (footprint "smart bracelet:RES0201")
      (description "0201WMF4701TEE\r\n精度: ±1%\r\n功率: 50mW")
      (fields
        (field (name "BOM_SUPPLIER PART") "C2989113")
        (field (name "BOM_MANUFACTURER PART") "TC0325B1000T5F")
        (field (name "CONTRIBUTOR") "lcsc")
      )
      (libsource (lib "smart bracelet") (part "RES0402"))
    )
    (comp (ref "R26")
      (value "0Ω")
      (footprint "smart bracelet:RES0201")
      (description "RC0201FR-070RL\r\n品牌: YAGEO(国巨)\r\n封装: 0201\r\n电阻类型: 厚膜电阻\r\n阻值: 0Ω\r\n精度: ±1%\r\n功率: 50mW")
      (fields
        (field (name "BOM_MANUFACTURER PART") "ERJ3GEY0R00V")
        (field (name "BOM_SUPPLIER PART") "C122704")
      )
      (libsource (lib "smart bracelet") (part "0Ω"))
    )
    (comp (ref "R27")
      (value "10k")
      (footprint "smart bracelet:RES0201")
      (description "0201WMF1002TEE\r\n精度: ±1%\r\n功率: 50mW")
      (fields
        (field (name "BOM_SUPPLIER PART") "C2989113")
        (field (name "BOM_MANUFACTURER PART") "TC0325B1000T5F")
        (field (name "CONTRIBUTOR") "lcsc")
      )
      (libsource (lib "smart bracelet") (part "RES0201"))
    )
    (comp (ref "R28")
      (value "4.7k")
      (footprint "smart bracelet:RES0201")
      (description "0201WMF4701TEE\r\n精度: ±1%\r\n功率: 50mW")
      (fields
        (field (name "BOM_SUPPLIER PART") "C2989113")
        (field (name "BOM_MANUFACTURER PART") "TC0325B1000T5F")
        (field (name "CONTRIBUTOR") "lcsc")
      )
      (libsource (lib "smart bracelet") (part "RES0402"))
    )
    (comp (ref "R29")
      (value "4.7k")
      (footprint "smart bracelet:RES0201")
      (description "0201WMF4701TEE\r\n精度: ±1%\r\n功率: 50mW")
      (fields
        (field (name "BOM_SUPPLIER PART") "C2989113")
        (field (name "BOM_MANUFACTURER PART") "TC0325B1000T5F")
        (field (name "CONTRIBUTOR") "lcsc")
      )
      (libsource (lib "smart bracelet") (part "RES0402"))
    )
    (comp (ref "R30")
      (value "4.7k")
      (footprint "smart bracelet:RES0201")
      (description "0201WMF4701TEE\r\n精度: ±1%\r\n功率: 50mW")
      (fields
        (field (name "BOM_SUPPLIER PART") "C2989113")
        (field (name "BOM_MANUFACTURER PART") "TC0325B1000T5F")
        (field (name "CONTRIBUTOR") "lcsc")
      )
      (libsource (lib "smart bracelet") (part "RES0402"))
    )
    (comp (ref "R31")
      (value "4.7k")
      (footprint "smart bracelet:RES0201")
      (description "0201WMF4701TEE\r\n精度: ±1%\r\n功率: 50mW")
      (fields
        (field (name "BOM_SUPPLIER PART") "C2989113")
        (field (name "BOM_MANUFACTURER PART") "TC0325B1000T5F")
        (field (name "CONTRIBUTOR") "lcsc")
      )
      (libsource (lib "smart bracelet") (part "RES0402"))
    )
    (comp (ref "R44")
      (value "0Ω")
      (footprint "smart bracelet:RES0201")
      (description "0201WMF0000TEE\r\n精度: ±1%\r\n功率: 50mW")
      (fields
        (field (name "BOM_MANUFACTURER PART") "ERJ3GEY0R00V")
        (field (name "BOM_SUPPLIER PART") "C122704")
      )
      (libsource (lib "smart bracelet") (part "0Ω"))
    )
    (comp (ref "R45")
      (value "1.5K")
      (footprint "smart bracelet:RES0201")
      (description "RC0201FR-071K5L\r\n品牌: YAGEO(国巨)\r\n封装: 0201\r\n电阻类型: 厚膜电阻\r\n阻值: 1.5kΩ\r\n精度: ±1%\r\n功率: 50mW")
      (fields
        (field (name "BOM_SUPPLIER PART") "C2989113")
        (field (name "BOM_MANUFACTURER PART") "TC0325B1000T5F")
        (field (name "CONTRIBUTOR") "lcsc")
      )
      (libsource (lib "smart bracelet") (part "RES0201"))
    )
    (comp (ref "R46")
      (value "4.7k")
      (footprint "smart bracelet:RES0201")
      (description "0201WMF4701TEE\r\n精度: ±1%\r\n功率: 50mW")
      (fields
        (field (name "BOM_SUPPLIER PART") "C2989113")
        (field (name "BOM_MANUFACTURER PART") "TC0325B1000T5F")
        (field (name "CONTRIBUTOR") "lcsc")
      )
      (libsource (lib "smart bracelet") (part "RES0402"))
    )
    (comp (ref "R47")
      (value "200k")
      (footprint "smart bracelet:RES0201")
      (description "RC0201FR-07200KL\r\n品牌: YAGEO(国巨)\r\n封装: 0201\r\n电阻类型: 厚膜电阻\r\n阻值: 200kΩ\r\n精度: ±1%\r\n功率: 50mW")
      (fields
        (field (name "BOM_SUPPLIER PART") "C2989113")
        (field (name "BOM_MANUFACTURER PART") "TC0325B1000T5F")
        (field (name "CONTRIBUTOR") "lcsc")
      )
      (libsource (lib "smart bracelet") (part "RES0201"))
    )
    (comp (ref "R48")
      (value "4.7k")
      (footprint "smart bracelet:RES0201")
      (description "0201WMF4701TEE\r\n精度: ±1%\r\n功率: 50mW")
      (fields
        (field (name "BOM_SUPPLIER PART") "C2989113")
        (field (name "BOM_MANUFACTURER PART") "TC0325B1000T5F")
        (field (name "CONTRIBUTOR") "lcsc")
      )
      (libsource (lib "smart bracelet") (part "RES0402"))
    )
    (comp (ref "R49")
      (value "4.7k")
      (footprint "smart bracelet:RES0201")
      (description "0201WMF4701TEE\r\n精度: ±1%\r\n功率: 50mW")
      (fields
        (field (name "BOM_SUPPLIER PART") "C2989113")
        (field (name "BOM_MANUFACTURER PART") "TC0325B1000T5F")
        (field (name "CONTRIBUTOR") "lcsc")
      )
      (libsource (lib "smart bracelet") (part "RES0402"))
    )
    (comp (ref "R50")
      (value "4.7k")
      (footprint "smart bracelet:RES0201")
      (description "0201WMF4701TEE\r\n精度: ±1%\r\n功率: 50mW")
      (fields
        (field (name "BOM_SUPPLIER PART") "C2989113")
        (field (name "BOM_MANUFACTURER PART") "TC0325B1000T5F")
        (field (name "CONTRIBUTOR") "lcsc")
      )
      (libsource (lib "smart bracelet") (part "RES0402"))
    )
    (comp (ref "R51")
      (value "4.7k")
      (footprint "smart bracelet:RES0201")
      (description "0201WMF4701TEE\r\n精度: ±1%\r\n功率: 50mW")
      (fields
        (field (name "BOM_SUPPLIER PART") "C2989113")
        (field (name "BOM_MANUFACTURER PART") "TC0325B1000T5F")
        (field (name "CONTRIBUTOR") "lcsc")
      )
      (libsource (lib "smart bracelet") (part "RES0402"))
    )
    (comp (ref "R52")
      (value "4.7k")
      (footprint "smart bracelet:RES0201")
      (description "0201WMF4701TEE\r\n精度: ±1%\r\n功率: 50mW")
      (fields
        (field (name "BOM_SUPPLIER PART") "C2989113")
        (field (name "BOM_MANUFACTURER PART") "TC0325B1000T5F")
        (field (name "CONTRIBUTOR") "lcsc")
      )
      (libsource (lib "smart bracelet") (part "RES0402"))
    )
    (comp (ref "R53")
      (value "4.7k")
      (footprint "smart bracelet:RES0201")
      (description "0201WMF4701TEE\r\n精度: ±1%\r\n功率: 50mW")
      (fields
        (field (name "BOM_SUPPLIER PART") "C2989113")
        (field (name "BOM_MANUFACTURER PART") "TC0325B1000T5F")
        (field (name "CONTRIBUTOR") "lcsc")
      )
      (libsource (lib "smart bracelet") (part "RES0402"))
    )
    (comp (ref "R54")
      (value "4.7k")
      (footprint "smart bracelet:RES0201")
      (description "0201WMF4701TEE\r\n精度: ±1%\r\n功率: 50mW")
      (fields
        (field (name "BOM_SUPPLIER PART") "C2989113")
        (field (name "BOM_MANUFACTURER PART") "TC0325B1000T5F")
        (field (name "CONTRIBUTOR") "lcsc")
      )
      (libsource (lib "smart bracelet") (part "RES0402"))
    )
    (comp (ref "R55")
      (value "4.7k")
      (footprint "smart bracelet:RES0201")
      (description "0201WMF4701TEE\r\n精度: ±1%\r\n功率: 50mW")
      (fields
        (field (name "BOM_SUPPLIER PART") "C2989113")
        (field (name "BOM_MANUFACTURER PART") "TC0325B1000T5F")
        (field (name "CONTRIBUTOR") "lcsc")
      )
      (libsource (lib "smart bracelet") (part "RES0402"))
    )
    (comp (ref "R56")
      (value "4.7k")
      (footprint "smart bracelet:RES0201")
      (description "0201WMF4701TEE\r\n精度: ±1%\r\n功率: 50mW")
      (fields
        (field (name "BOM_SUPPLIER PART") "C2989113")
        (field (name "BOM_MANUFACTURER PART") "TC0325B1000T5F")
        (field (name "CONTRIBUTOR") "lcsc")
      )
      (libsource (lib "smart bracelet") (part "RES0402"))
    )
    (comp (ref "R57")
      (value "4.7k")
      (footprint "smart bracelet:RES0201")
      (description "0201WMF4701TEE\r\n精度: ±1%\r\n功率: 50mW")
      (fields
        (field (name "BOM_SUPPLIER PART") "C2989113")
        (field (name "BOM_MANUFACTURER PART") "TC0325B1000T5F")
        (field (name "CONTRIBUTOR") "lcsc")
      )
      (libsource (lib "smart bracelet") (part "RES0402"))
    )
    (comp (ref "R58")
      (value "200k")
      (footprint "smart bracelet:RES0201")
      (description "RC0201FR-07200KL\r\n品牌: YAGEO(国巨)\r\n封装: 0201\r\n电阻类型: 厚膜电阻\r\n阻值: 200kΩ\r\n精度: ±1%\r\n功率: 50mW")
      (fields
        (field (name "BOM_SUPPLIER PART") "C2989113")
        (field (name "BOM_MANUFACTURER PART") "TC0325B1000T5F")
        (field (name "CONTRIBUTOR") "lcsc")
      )
      (libsource (lib "smart bracelet") (part "RES0201"))
    )
    (comp (ref "R59")
      (value "200k")
      (footprint "smart bracelet:RES0201")
      (description "RC0201FR-07200KL\r\n品牌: YAGEO(国巨)\r\n封装: 0201\r\n电阻类型: 厚膜电阻\r\n阻值: 200kΩ\r\n精度: ±1%\r\n功率: 50mW")
      (fields
        (field (name "BOM_SUPPLIER PART") "C2989113")
        (field (name "BOM_MANUFACTURER PART") "TC0325B1000T5F")
        (field (name "CONTRIBUTOR") "lcsc")
      )
      (libsource (lib "smart bracelet") (part "RES0201"))
    )
    (comp (ref "R60")
      (value "100kΩ")
      (footprint "smart bracelet:RES0201")
      (description "0201WMF1003TEE\r\n精度: ±1%\r\n功率: 50mW")
      (fields
        (field (name "BOM_MANUFACTURER PART") "ERJ3GEY0R00V")
        (field (name "BOM_SUPPLIER PART") "C122704")
      )
      (libsource (lib "smart bracelet") (part "0Ω"))
    )
    (comp (ref "R61")
      (value "100kΩ")
      (footprint "smart bracelet:RES0201")
      (description "0201WMF1003TEE\r\n精度: ±1%\r\n功率: 50mW")
      (fields
        (field (name "BOM_MANUFACTURER PART") "ERJ3GEY0R00V")
        (field (name "BOM_SUPPLIER PART") "C122704")
      )
      (libsource (lib "smart bracelet") (part "0Ω"))
    )
    (comp (ref "RF1")
      (value "IPEX-4")
      (footprint "smart bracelet:IPEX-SMD_4P-L1.8-W1.7-LS2.0")
      (fields (field (name "MANUFACTURER") "Ziisor(致哲)") (field (name "CONTRIBUTOR") "lcsc"))
      (libsource (lib "smart bracelet") (part "IPEX-4"))
    )
    (comp (ref "TP1") (value "SWO") (footprint "Testpoint") (libsource (lib "smart bracelet") (part "TP")))
    (comp (ref "TP2")
      (value "RTC_CLKOUT")
      (footprint "Testpoint")
      (libsource (lib "smart bracelet") (part "TP"))
    )
    (comp (ref "U1")
      (value "AMA4B2KL-KXR")
      (footprint "BGA131_0P35_4P7x4P7_AP4BL")
      (description "None")
      (fields (field (name "MANUFACTURER") "AMBIQ"))
      (libsource (lib "AMA4BLEVB") (part "APOLLO4BLKXR"))
    )
    (comp (ref "U2")
      (value "AM1805AQ")
      (footprint "QFN50P300X300X90-17N")
      (libsource (lib "smart bracelet") (part "AM1805AQ"))
    )
    (comp (ref "U3")
      (value "GD5F1GQ5REWIG")
      (footprint "WSON-8_L6.0-W5.0-P1.27-BL-EP")
      (libsource (lib "smart bracelet") (part "GD5F1GQ5REWIG"))
    )
    (comp (ref "U4")
      (value "APS6404L-SQN-ZR")
      (footprint "PSON50P200X300X50-9N")
      (description "DRAM IoT RAM 64Mb QSPI (x 1,x4) SDR 144MHz, 1")
      (fields (field (name "MF") "AP Memory") (field (name "MP") "APS6404L-3SQR-ZR"))
      (libsource (lib "smart bracelet") (part "APS6404L-3SQR-ZR"))
    )
    (comp (ref "U5")
      (value "MAX98357AETE+T")
      (footprint "smart bracelet:TQFN-16_L3.0-W3.0-P0.50-BL-EP1.5")
      (fields (field (name "MANUFACTURER") "ADI(亚德诺)/MAXIM(美信)") (field (name "CONTRIBUTOR") "LCSC"))
      (libsource (lib "smart bracelet") (part "MAX98357AETE+T"))
    )
    (comp (ref "U6")
      (value "PCA9306DQER")
      (footprint "X2SON-8_L1.4-W1.0-P0.35-BL")
      (fields (field (name "MANUFACTURER") "TI(德州仪器)") (field (name "NAME") "PCA9306DQER"))
      (libsource (lib "smart bracelet") (part "PCA9306DQER"))
    )
    (comp (ref "U7")
      (value "PCA9306DQER")
      (footprint "X2SON-8_L1.4-W1.0-P0.35-BL")
      (fields (field (name "MANUFACTURER") "TI(德州仪器)") (field (name "NAME") "PCA9306DQER"))
      (libsource (lib "smart bracelet") (part "PCA9306DQER"))
    )
    (comp (ref "U8")
      (value "PCA9306DQER")
      (footprint "X2SON-8_L1.4-W1.0-P0.35-BL")
      (fields (field (name "MANUFACTURER") "TI(德州仪器)") (field (name "NAME") "PCA9306DQER"))
      (libsource (lib "smart bracelet") (part "PCA9306DQER"))
    )
    (comp (ref "X1")
      (value "32.768kHz")
      (footprint "OSC-SMD_2P-L1.6-W1.0")
      (fields
        (field (name "MANUFACTURER") "EPSON(爱普生)")
        (field (name "MANUFACTURER PART") "X1A0001210005")
        (field (name "NAME") "32.768kHz")
      )
      (libsource (lib "smart bracelet") (part "7BG03276A39"))
    )
    (comp (ref "X2")
      (value "32MHZ")
      (footprint "CRYSTAL-SMD_4P-L1.6-W1.2-BL")
      (description "1S32000054")
      (libsource (lib "smart bracelet") (part "1S32000054"))
    )
    (comp (ref "X3")
      (value "32.768kHz")
      (footprint "OSC-SMD_2P-L1.6-W1.0")
      (description "7BG03276A39")
      (fields
        (field (name "MANUFACTURER") "EPSON(爱普生)")
        (field (name "MANUFACTURER PART") "X1A0001210005")
        (field (name "NAME") "32.768kHz")
      )
      (libsource (lib "smart bracelet") (part "7BG03276A39"))
    )
  )
  (nets
    (net (code "1") (name "/A_LCD_LEDK") (class "Default")
      (node (ref "FPC1") (pin "2") (pinfunction "2_2") (pintype "passive"))
      (node (ref "R18") (pin "2") (pinfunction "2_2") (pintype "passive"))
    )
    (net (code "2") (name "/A_LCD_TP_SCL") (class "Default")
      (node (ref "FPC1") (pin "13") (pinfunction "13_13") (pintype "passive"))
      (node (ref "R50") (pin "2") (pinfunction "2_2") (pintype "passive"))
      (node (ref "U7") (pin "6") (pinfunction "SCL2_6") (pintype "passive"))
    )
    (net (code "3") (name "/A_LCD_TP_SDA") (class "Default")
      (node (ref "FPC1") (pin "14") (pinfunction "14_14") (pintype "passive"))
      (node (ref "R51") (pin "2") (pinfunction "2_2") (pintype "passive"))
      (node (ref "U7") (pin "5") (pinfunction "SDA2_5") (pintype "passive"))
    )
    (net (code "4") (name "/A_LCD_TP_TINT") (class "Default")
      (node (ref "FPC1") (pin "16") (pinfunction "16_16") (pintype "passive"))
      (node (ref "R53") (pin "2") (pinfunction "2_2") (pintype "passive"))
      (node (ref "U8") (pin "5") (pinfunction "SDA2_5") (pintype "passive"))
    )
    (net (code "5") (name "/A_LCD_TP_TRST") (class "Default")
      (node (ref "FPC1") (pin "15") (pinfunction "15_15") (pintype "passive"))
      (node (ref "R52") (pin "2") (pinfunction "2_2") (pintype "passive"))
      (node (ref "U8") (pin "6") (pinfunction "SCL2_6") (pintype "passive"))
    )
    (net (code "6") (name "/Button1") (class "Default")
      (node (ref "R4") (pin "1") (pinfunction "1_1") (pintype "passive"))
      (node (ref "U1") (pin "F12") (pinfunction "GPIO38_F12") (pintype "passive"))
    )
    (net (code "7") (name "/Button1_P") (class "Default")
      (node (ref "C24") (pin "1") (pinfunction "1_1") (pintype "passive"))
      (node (ref "J2") (pin "1") (pinfunction "1_1") (pintype "passive"))
      (node (ref "Q3") (pin "2") (pinfunction "S_2") (pintype "passive"))
      (node (ref "R4") (pin "2") (pinfunction "2_2") (pintype "passive"))
      (node (ref "R5") (pin "2") (pinfunction "2_2") (pintype "passive"))
    )
    (net (code "8") (name "/Button2") (class "Default")
      (node (ref "R6") (pin "1") (pinfunction "1_1") (pintype "passive"))
      (node (ref "U1") (pin "F11") (pinfunction "GPIO37_F11") (pintype "passive"))
    )
    (net (code "9") (name "/Button2_M") (class "Default")
      (node (ref "C25") (pin "1") (pinfunction "1_1") (pintype "passive"))
      (node (ref "J2") (pin "2") (pinfunction "2_2") (pintype "passive"))
      (node (ref "R6") (pin "2") (pinfunction "2_2") (pintype "passive"))
      (node (ref "R7") (pin "2") (pinfunction "2_2") (pintype "passive"))
    )
    (net (code "10") (name "/ENS1_SUP_EN") (class "Default")
      (node (ref "J9") (pin "4") (pinfunction "4_4") (pintype "passive"))
      (node (ref "U1") (pin "D5") (pinfunction "GPIO13_D5") (pintype "passive"))
    )
    (net (code "11") (name "/ES_RX") (class "Default")
      (node (ref "J8") (pin "9") (pinfunction "9_9") (pintype "passive"))
      (node (ref "R49") (pin "2") (pinfunction "2_2") (pintype "passive"))
      (node (ref "U6") (pin "5") (pinfunction "SDA2_5") (pintype "passive"))
    )
    (net (code "12") (name "/ES_TX") (class "Default")
      (node (ref "J8") (pin "10") (pinfunction "10_10") (pintype "passive"))
      (node (ref "R48") (pin "2") (pinfunction "2_2") (pintype "passive"))
      (node (ref "U6") (pin "6") (pinfunction "SCL2_6") (pintype "passive"))
    )
    (net (code "13") (name "/FG_GPOUT") (class "Default")
      (node (ref "J9") (pin "10") (pinfunction "10_10") (pintype "passive"))
      (node (ref "U1") (pin "B7") (pinfunction "GPIO68_B7") (pintype "passive"))
    )
    (net (code "14") (name "/GH3020_INT") (class "Default")
      (node (ref "J8") (pin "8") (pinfunction "8_8") (pintype "passive"))
      (node (ref "U1") (pin "J2") (pinfunction "GPIO104_J2") (pintype "passive"))
    )
    (net (code "15") (name "/GH3020_RES") (class "Default")
      (node (ref "J8") (pin "7") (pinfunction "7_7") (pintype "passive"))
      (node (ref "U1") (pin "K2") (pinfunction "GPIO91_K2") (pintype "passive"))
    )
    (net (code "16") (name "/I2C1_SCL") (class "Default")
      (node (ref "J8") (pin "5") (pinfunction "5_5") (pintype "passive"))
      (node (ref "R30") (pin "1") (pinfunction "1_1") (pintype "passive"))
      (node (ref "U1") (pin "E8") (pinfunction "GPIO08_E8") (pintype "passive"))
    )
    (net (code "17") (name "/I2C1_SDA") (class "Default")
      (node (ref "J8") (pin "6") (pinfunction "6_6") (pintype "passive"))
      (node (ref "R31") (pin "1") (pinfunction "1_1") (pintype "passive"))
      (node (ref "U1") (pin "E7") (pinfunction "GPIO09_E7") (pintype "passive"))
    )
    (net (code "18") (name "/I2C2_SCL") (class "Default")
      (node (ref "R20") (pin "1") (pinfunction "1_1") (pintype "passive"))
      (node (ref "U1") (pin "K5") (pinfunction "GPIO25_K5") (pintype "passive"))
      (node (ref "U7") (pin "3") (pinfunction "SCL1_3") (pintype "passive"))
    )
    (net (code "19") (name "/I2C2_SDA") (class "Default")
      (node (ref "R21") (pin "1") (pinfunction "1_1") (pintype "passive"))
      (node (ref "U1") (pin "L5") (pinfunction "GPIO26_L5") (pintype "passive"))
      (node (ref "U7") (pin "4") (pinfunction "SDA1_4") (pintype "passive"))
    )
    (net (code "20") (name "/I2C3_SCL") (class "Default")
      (node (ref "J8") (pin "1") (pinfunction "1_1") (pintype "passive"))
      (node (ref "R22") (pin "1") (pinfunction "1_1") (pintype "passive"))
      (node (ref "U1") (pin "H2") (pinfunction "GPIO31_H2") (pintype "passive"))
    )
    (net (code "21") (name "/I2C3_SDA") (class "Default")
      (node (ref "J8") (pin "2") (pinfunction "2_2") (pintype "passive"))
      (node (ref "R23") (pin "1") (pinfunction "1_1") (pintype "passive"))
      (node (ref "U1") (pin "G2") (pinfunction "GPIO32_G2") (pintype "passive"))
    )
    (net (code "22") (name "/I2C5_SCL") (class "Default")
      (node (ref "J8") (pin "3") (pinfunction "3_3") (pintype "passive"))
      (node (ref "R24") (pin "1") (pinfunction "1_1") (pintype "passive"))
      (node (ref "U1") (pin "F1") (pinfunction "GPIO47_F1") (pintype "passive"))
      (node (ref "U2") (pin "7") (pinfunction "SCL_7") (pintype "passive"))
    )
    (net (code "23") (name "/I2C5_SDA") (class "Default")
      (node (ref "J8") (pin "4") (pinfunction "4_4") (pintype "passive"))
      (node (ref "R25") (pin "1") (pinfunction "1_1") (pintype "passive"))
      (node (ref "U1") (pin "E1") (pinfunction "GPIO48_E1") (pintype "passive"))
      (node (ref "U2") (pin "6") (pinfunction "SDA_6") (pintype "passive"))
    )
    (net (code "24") (name "/I2C7_SCL") (class "Default")
      (node (ref "J3") (pin "3") (pinfunction "3_3") (pintype "passive"))
      (node (ref "R28") (pin "1") (pinfunction "1_1") (pintype "passive"))
      (node (ref "U1") (pin "F3") (pinfunction "GPIO22_F3") (pintype "passive"))
    )
    (net (code "25") (name "/I2C7_SDA") (class "Default")
      (node (ref "J3") (pin "4") (pinfunction "4_4") (pintype "passive"))
      (node (ref "R29") (pin "1") (pinfunction "1_1") (pintype "passive"))
      (node (ref "U1") (pin "F2") (pinfunction "GPIO23_F2") (pintype "passive"))
    )
    (net (code "26") (name "/I2S0_CLK") (class "Default")
      (node (ref "R14") (pin "1") (pinfunction "1_1") (pintype "passive"))
      (node (ref "U1") (pin "H4") (pinfunction "GPIO05_H4") (pintype "passive"))
    )
    (net (code "27") (name "/I2S0_SDOUT") (class "Default")
      (node (ref "R11") (pin "2") (pinfunction "2_2") (pintype "passive"))
      (node (ref "U1") (pin "J5") (pinfunction "GPIO06_J5") (pintype "passive"))
    )
    (net (code "28") (name "/I2S0_SD_MODE#") (class "Default")
      (node (ref "R13") (pin "1") (pinfunction "1_1") (pintype "passive"))
      (node (ref "U1") (pin "H3") (pinfunction "GPIO00_H3") (pintype "passive"))
      (node (ref "U5") (pin "4") (pinfunction "SD_MODE#_4") (pintype "passive"))
    )
    (net (code "29") (name "/I2S0_WS") (class "Default")
      (node (ref "U1") (pin "J6") (pinfunction "GPIO07_J6") (pintype "passive"))
      (node (ref "U5") (pin "14") (pinfunction "LRCLK_14") (pintype "passive"))
    )
    (net (code "30") (name "/ICM_INT1") (class "Default")
      (node (ref "J9") (pin "1") (pinfunction "1_1") (pintype "passive"))
      (node (ref "U1") (pin "D6") (pinfunction "GPIO14_D6") (pintype "passive"))
    )
    (net (code "31") (name "/LCD_CS") (class "Default")
      (node (ref "FPC1") (pin "8") (pinfunction "8_8") (pintype "passive"))
      (node (ref "U1") (pin "L11") (pinfunction "GPIO78_L11") (pintype "passive"))
    )
    (net (code "32") (name "/LCD_DC") (class "Default")
      (node (ref "FPC1") (pin "7") (pinfunction "7_7") (pintype "passive"))
      (node (ref "U1") (pin "L10") (pinfunction "GPIO81_L10") (pintype "passive"))
    )
    (net (code "33") (name "/LCD_LEDK") (class "Default")
      (node (ref "R17") (pin "1") (pinfunction "1_1") (pintype "passive"))
      (node (ref "U1") (pin "K10") (pinfunction "GPIO80_K10") (pintype "passive"))
    )
    (net (code "34") (name "/LCD_RES") (class "Default")
      (node (ref "FPC1") (pin "11") (pinfunction "11_11") (pintype "passive"))
      (node (ref "U1") (pin "M11") (pinfunction "GPIO79_M11") (pintype "passive"))
    )
    (net (code "35") (name "/LCD_TP_TINT") (class "Default")
      (node (ref "R57") (pin "2") (pinfunction "2_2") (pintype "passive"))
      (node (ref "U1") (pin "H9") (pinfunction "GPIO85_H9") (pintype "passive"))
      (node (ref "U8") (pin "4") (pinfunction "SDA1_4") (pintype "passive"))
    )
    (net (code "36") (name "/LCD_TP_TRST") (class "Default")
      (node (ref "R56") (pin "2") (pinfunction "2_2") (pintype "passive"))
      (node (ref "U1") (pin "J9") (pinfunction "GPIO84_J9") (pintype "passive"))
      (node (ref "U8") (pin "3") (pinfunction "SCL1_3") (pintype "passive"))
    )
    (net (code "37") (name "/MSPI0_FLASH_CS#") (class "Default")
      (node (ref "R10") (pin "1") (pinfunction "1_1") (pintype "passive"))
      (node (ref "U1") (pin "D8") (pinfunction "GPIO73_D8") (pintype "passive"))
      (node (ref "U3") (pin "1") (pinfunction "CS#_1") (pintype "passive"))
    )
    (net (code "38") (name "/MSPI0_FLASH_SCLK") (class "Default")
      (node (ref "U1") (pin "C8") (pinfunction "GPIO72_C8") (pintype "passive"))
      (node (ref "U3") (pin "6") (pinfunction "SCLK_6") (pintype "passive"))
    )
    (net (code "39") (name "/MSPI0_FLASH_SIO0") (class "Default")
      (node (ref "U1") (pin "B6") (pinfunction "GPIO64_B6") (pintype "passive"))
      (node (ref "U3") (pin "5") (pinfunction "SI/SIO0_5") (pintype "passive"))
    )
    (net (code "40") (name "/MSPI0_FLASH_SIO1") (class "Default")
      (node (ref "U1") (pin "A7") (pinfunction "GPIO65_A7") (pintype "passive"))
      (node (ref "U3") (pin "2") (pinfunction "SO/SIO1_2") (pintype "passive"))
    )
    (net (code "41") (name "/MSPI0_FLASH_SIO2") (class "Default")
      (node (ref "U1") (pin "A8") (pinfunction "GPIO66_A8") (pintype "passive"))
      (node (ref "U3") (pin "3") (pinfunction "WP#/SIO2_3") (pintype "passive"))
    )
    (net (code "42") (name "/MSPI0_FLASH_SIO3") (class "Default")
      (node (ref "U1") (pin "C6") (pinfunction "GPIO67_C6") (pintype "passive"))
      (node (ref "U3") (pin "7") (pinfunction "HOLD#/SIO3_7") (pintype "passive"))
    )
    (net (code "43") (name "/MSPI2_PSRAM_CE#") (class "Default")
      (node (ref "U1") (pin "K9") (pinfunction "GPIO83_K9") (pintype "passive"))
      (node (ref "U4") (pin "1") (pinfunction "~{CE}_1") (pintype "input"))
    )
    (net (code "44") (name "/MSPI2_PSRAM_SCLK") (class "Default")
      (node (ref "U1") (pin "L9") (pinfunction "GPIO82_L9") (pintype "passive"))
      (node (ref "U4") (pin "6") (pinfunction "SCLK_6") (pintype "input"))
    )
    (net (code "45") (name "/MSPI2_PSRAM_SIO0") (class "Default")
      (node (ref "U1") (pin "G11") (pinfunction "GPIO74_G11") (pintype "passive"))
      (node (ref "U4") (pin "5") (pinfunction "SI/SIO(0)_5") (pintype "bidirectional"))
    )
    (net (code "46") (name "/MSPI2_PSRAM_SIO1") (class "Default")
      (node (ref "U1") (pin "H11") (pinfunction "GPIO75_H11") (pintype "passive"))
      (node (ref "U4") (pin "2") (pinfunction "SO/SIO(1)_2") (pintype "bidirectional"))
    )
    (net (code "47") (name "/MSPI2_PSRAM_SIO2") (class "Default")
      (node (ref "U1") (pin "J11") (pinfunction "GPIO76_J11") (pintype "passive"))
      (node (ref "U4") (pin "3") (pinfunction "SIO(2)_3") (pintype "bidirectional"))
    )
    (net (code "48") (name "/MSPI2_PSRAM_SIO3") (class "Default")
      (node (ref "U1") (pin "K11") (pinfunction "GPIO77_K11") (pintype "passive"))
      (node (ref "U4") (pin "7") (pinfunction "SIO(3)_7") (pintype "bidirectional"))
    )
    (net (code "49") (name "/PDM0_MIC_CLK") (class "Default")
      (node (ref "J2") (pin "3") (pinfunction "3_3") (pintype "passive"))
      (node (ref "U1") (pin "A9") (pinfunction "GPIO50_A9") (pintype "passive"))
    )
    (net (code "50") (name "/PDM0_MIC_LR") (class "Default")
      (node (ref "J2") (pin "4") (pinfunction "4_4") (pintype "passive"))
      (node (ref "U1") (pin "B8") (pinfunction "GPIO69_B8") (pintype "passive"))
    )
    (net (code "51") (name "/PDM0_MIC_SDOUT") (class "Default")
      (node (ref "J2") (pin "7") (pinfunction "7_7") (pintype "passive"))
      (node (ref "U1") (pin "B9") (pinfunction "GPIO51_B9") (pintype "passive"))
    )
    (net (code "52") (name "/PMIC_INT") (class "Default")
      (node (ref "J9") (pin "9") (pinfunction "9_9") (pintype "passive"))
      (node (ref "U1") (pin "B4") (pinfunction "GPIO12_B4") (pintype "passive"))
    )
    (net (code "53") (name "/PWM_MOTOR") (class "Default")
      (node (ref "R8") (pin "2") (pinfunction "2_2") (pintype "passive"))
      (node (ref "U1") (pin "C3") (pinfunction "GPIO19_C3") (pintype "passive"))
    )
    (net (code "54") (name "/RTC_nIRQ") (class "Default")
      (node (ref "R46") (pin "1") (pinfunction "1_1") (pintype "passive"))
      (node (ref "U1") (pin "E5") (pinfunction "GPIO15_E5") (pintype "passive"))
      (node (ref "U2") (pin "11") (pinfunction "FOUT/nIRQ_11") (pintype "passive"))
    )
    (net (code "55") (name "/SPI6_MOSI") (class "Default")
      (node (ref "FPC1") (pin "10") (pinfunction "10_10") (pintype "passive"))
      (node (ref "U1") (pin "L6") (pinfunction "GPIO62_L6") (pintype "passive"))
    )
    (net (code "56") (name "/SPI6_SCK") (class "Default")
      (node (ref "FPC1") (pin "9") (pinfunction "9_9") (pintype "passive"))
      (node (ref "U1") (pin "K6") (pinfunction "GPIO61_K6") (pintype "passive"))
    )
    (net (code "57") (name "/SPK+") (class "Default")
      (node (ref "C31") (pin "2") (pinfunction "2_2") (pintype "passive"))
      (node (ref "J3") (pin "5") (pinfunction "5_5") (pintype "passive"))
      (node (ref "L5") (pin "2") (pinfunction "2_2") (pintype "passive"))
    )
    (net (code "58") (name "/SPK-") (class "Default")
      (node (ref "C30") (pin "2") (pinfunction "2_2") (pintype "passive"))
      (node (ref "J3") (pin "6") (pinfunction "6_6") (pintype "passive"))
      (node (ref "L6") (pin "2") (pinfunction "2_2") (pintype "passive"))
    )
    (net (code "59") (name "/SWDCLK") (class "Default")
      (node (ref "J7") (pin "2") (pinfunction "2_2") (pintype "passive"))
      (node (ref "R60") (pin "1") (pinfunction "1_1") (pintype "passive"))
      (node (ref "U1") (pin "K3") (pinfunction "GPIO20_K3") (pintype "passive"))
    )
    (net (code "60") (name "/SWDIO") (class "Default")
      (node (ref "J7") (pin "3") (pinfunction "3_3") (pintype "passive"))
      (node (ref "R61") (pin "2") (pinfunction "2_2") (pintype "passive"))
      (node (ref "U1") (pin "J3") (pinfunction "GPIO21_J3") (pintype "passive"))
    )
    (net (code "61") (name "/SYS_RST") (class "Default")
      (node (ref "J9") (pin "8") (pinfunction "8_8") (pintype "passive"))
      (node (ref "Q3") (pin "3") (pinfunction "D_3") (pintype "passive"))
    )
    (net (code "62") (name "/TMP") (class "Default")
      (node (ref "J9") (pin "2") (pinfunction "2_2") (pintype "passive"))
      (node (ref "R2") (pin "1") (pinfunction "1_1") (pintype "passive"))
      (node (ref "U1") (pin "D3") (pinfunction "GPIO18_D3") (pintype "passive"))
    )
    (net (code "63") (name "/UART2_RX") (class "Default")
      (node (ref "R55") (pin "2") (pinfunction "2_2") (pintype "passive"))
      (node (ref "U1") (pin "L4") (pinfunction "GPIO03_L4") (pintype "passive"))
      (node (ref "U6") (pin "4") (pinfunction "SDA1_4") (pintype "passive"))
    )
    (net (code "64") (name "/UART2_TX") (class "Default")
      (node (ref "R54") (pin "2") (pinfunction "2_2") (pintype "passive"))
      (node (ref "U1") (pin "J4") (pinfunction "GPIO01_J4") (pintype "passive"))
      (node (ref "U6") (pin "3") (pinfunction "SCL1_3") (pintype "passive"))
    )
    (net (code "65") (name "/UART3_RX") (class "Default")
      (node (ref "J6") (pin "2") (pinfunction "2_2") (pintype "passive"))
      (node (ref "U1") (pin "E10") (pinfunction "GPIO44_E10") (pintype "passive"))
    )
    (net (code "66") (name "/UART3_TX") (class "Default")
      (node (ref "J6") (pin "1") (pinfunction "1_1") (pintype "passive"))
      (node (ref "U1") (pin "D9") (pinfunction "GPIO42_D9") (pintype "passive"))
    )
    (net (code "67") (name "/VDD5V_EN") (class "Default")
      (node (ref "J9") (pin "3") (pinfunction "3_3") (pintype "passive"))
      (node (ref "U1") (pin "C5") (pinfunction "GPIO70_C5") (pintype "passive"))
    )
    (net (code "68") (name "/VDDF") (class "Default")
      (node (ref "C12") (pin "2") (pinfunction "2_2") (pintype "passive"))
      (node (ref "C9") (pin "2") (pinfunction "2_2") (pintype "passive"))
      (node (ref "U1") (pin "C2") (pinfunction "VDDF_C2") (pintype "passive"))
    )
    (net (code "69") (name "/VEM_INT") (class "Default")
      (node (ref "J3") (pin "1") (pinfunction "1_1") (pintype "passive"))
      (node (ref "R27") (pin "2") (pinfunction "2_2") (pintype "passive"))
      (node (ref "U1") (pin "C7") (pinfunction "GPIO71_C7") (pintype "passive"))
    )
    (net (code "70") (name "/nRST") (class "Default")
      (node (ref "C21") (pin "1") (pinfunction "1_1") (pintype "passive"))
      (node (ref "D1") (pin "1") (pinfunction "C_1") (pintype "passive"))
      (node (ref "J5") (pin "1") (pinfunction "1_1") (pintype "passive"))
      (node (ref "R3") (pin "1") (pinfunction "1_1") (pintype "passive"))
      (node (ref "U1") (pin "A6") (pinfunction "RSTN_A6") (pintype "passive"))
    )
    (net (code "71") (name "GND") (class "Default")
      (node (ref "C1") (pin "1") (pinfunction "1_1") (pintype "passive"))
      (node (ref "C10") (pin "1") (pinfunction "1_1") (pintype "passive"))
      (node (ref "C11") (pin "1") (pinfunction "1_1") (pintype "passive"))
      (node (ref "C13") (pin "2") (pinfunction "2_2") (pintype "passive"))
      (node (ref "C14") (pin "2") (pinfunction "2_2") (pintype "passive"))
      (node (ref "C15") (pin "2") (pinfunction "2_2") (pintype "passive"))
      (node (ref "C16") (pin "2") (pinfunction "2_2") (pintype "passive"))
      (node (ref "C17") (pin "1") (pinfunction "1_1") (pintype "passive"))
      (node (ref "C18") (pin "2") (pinfunction "2_2") (pintype "passive"))
      (node (ref "C19") (pin "2") (pinfunction "2_2") (pintype "passive"))
      (node (ref "C2") (pin "1") (pinfunction "1_1") (pintype "passive"))
      (node (ref "C20") (pin "2") (pinfunction "2_2") (pintype "passive"))
      (node (ref "C21") (pin "2") (pinfunction "2_2") (pintype "passive"))
      (node (ref "C24") (pin "2") (pinfunction "2_2") (pintype "passive"))
      (node (ref "C25") (pin "2") (pinfunction "2_2") (pintype "passive"))
      (node (ref "C26") (pin "2") (pinfunction "2_2") (pintype "passive"))
      (node (ref "C27") (pin "2") (pinfunction "2_2") (pintype "passive"))
      (node (ref "C28") (pin "2") (pinfunction "2_2") (pintype "passive"))
      (node (ref "C29") (pin "2") (pinfunction "2_2") (pintype "passive"))
      (node (ref "C3") (pin "1") (pinfunction "1_1") (pintype "passive"))
      (node (ref "C30") (pin "1") (pinfunction "1_1") (pintype "passive"))
      (node (ref "C31") (pin "1") (pinfunction "1_1") (pintype "passive"))
      (node (ref "C32") (pin "2") (pinfunction "2_2") (pintype "passive"))
      (node (ref "C33") (pin "2") (pinfunction "2_2") (pintype "passive"))
      (node (ref "C34") (pin "2") (pinfunction "2_2") (pintype "passive"))
      (node (ref "C35") (pin "2") (pinfunction "2_2") (pintype "passive"))
      (node (ref "C4") (pin "1") (pinfunction "1_1") (pintype "passive"))
      (node (ref "C41") (pin "2") (pinfunction "2_2") (pintype "passive"))
      (node (ref "C42") (pin "2") (pinfunction "2_2") (pintype "passive"))
      (node (ref "C43") (pin "2") (pinfunction "2_2") (pintype "passive"))
      (node (ref "C44") (pin "2") (pinfunction "2_2") (pintype "passive"))
      (node (ref "C45") (pin "2") (pinfunction "2_2") (pintype "passive"))
      (node (ref "C46") (pin "2") (pinfunction "2_2") (pintype "passive"))
      (node (ref "C47") (pin "1") (pinfunction "1_1") (pintype "passive"))
      (node (ref "C48") (pin "1") (pinfunction "1_1") (pintype "passive"))
      (node (ref "C49") (pin "2") (pinfunction "2_2") (pintype "passive"))
      (node (ref "C5") (pin "1") (pinfunction "1_1") (pintype "passive"))
      (node (ref "C50") (pin "2") (pinfunction "2_2") (pintype "passive"))
      (node (ref "C51") (pin "2") (pinfunction "2_2") (pintype "passive"))
      (node (ref "C6") (pin "1") (pinfunction "1_1") (pintype "passive"))
      (node (ref "C7") (pin "1") (pinfunction "1_1") (pintype "passive"))
      (node (ref "C8") (pin "1") (pinfunction "1_1") (pintype "passive"))
      (node (ref "C9") (pin "1") (pinfunction "1_1") (pintype "passive"))
      (node (ref "D1") (pin "2") (pinfunction "A_2") (pintype "passive"))
      (node (ref "D3") (pin "1") (pinfunction "1_1") (pintype "passive"))
      (node (ref "FPC1") (pin "1") (pinfunction "1_1") (pintype "passive"))
      (node (ref "FPC1") (pin "12") (pinfunction "12_12") (pintype "passive"))
      (node (ref "FPC1") (pin "18") (pinfunction "18_18") (pintype "passive"))
      (node (ref "FPC1") (pin "19") (pinfunction "19_19") (pintype "passive"))
      (node (ref "FPC1") (pin "20") (pinfunction "20_20") (pintype "passive"))
      (node (ref "FPC1") (pin "5") (pinfunction "5_5") (pintype "passive"))
      (node (ref "FPC1") (pin "6") (pinfunction "6_6") (pintype "passive"))
      (node (ref "J2") (pin "0") (pinfunction "0_0") (pintype "passive"))
      (node (ref "J2") (pin "5") (pinfunction "5_5") (pintype "passive"))
      (node (ref "J3") (pin "0") (pinfunction "0_0") (pintype "passive"))
      (node (ref "J3") (pin "2") (pinfunction "2_2") (pintype "passive"))
      (node (ref "J3") (pin "7") (pinfunction "7_7") (pintype "passive"))
      (node (ref "J5") (pin "2") (pinfunction "2_2") (pintype "passive"))
      (node (ref "J7") (pin "1") (pinfunction "1_1") (pintype "passive"))
      (node (ref "J8") (pin "11") (pinfunction "11_11") (pintype "passive"))
      (node (ref "J8") (pin "12") (pinfunction "12_12") (pintype "passive"))
      (node (ref "J8") (pin "15") (pinfunction "15_15") (pintype "passive"))
      (node (ref "J9") (pin "11") (pinfunction "11_11") (pintype "passive"))
      (node (ref "J9") (pin "12") (pinfunction "12_12") (pintype "passive"))
      (node (ref "J9") (pin "15") (pinfunction "15_15") (pintype "passive"))
      (node (ref "Q1") (pin "2") (pinfunction "S_2") (pintype "passive"))
      (node (ref "Q2") (pin "2") (pinfunction "E_2") (pintype "passive"))
      (node (ref "R12") (pin "2") (pinfunction "2_2") (pintype "passive"))
      (node (ref "R26") (pin "1") (pinfunction "1_1") (pintype "passive"))
      (node (ref "R60") (pin "2") (pinfunction "2_2") (pintype "passive"))
      (node (ref "R9") (pin "2") (pinfunction "2_2") (pintype "passive"))
      (node (ref "RF1") (pin "2") (pinfunction "2_2") (pintype "passive"))
      (node (ref "RF1") (pin "3") (pinfunction "3_3") (pintype "passive"))
      (node (ref "RF1") (pin "4") (pinfunction "4_4") (pintype "passive"))
      (node (ref "U1") (pin "B12") (pinfunction "VSSAUDA_B12") (pintype "passive"))
      (node (ref "U1") (pin "B2") (pinfunction "VSSP_B2") (pintype "passive"))
      (node (ref "U1") (pin "B5") (pinfunction "VSSA_B5") (pintype "passive"))
      (node (ref "U1") (pin "D2") (pinfunction "VSS_D2") (pintype "passive"))
      (node (ref "U1") (pin "E12") (pinfunction "VSSAUDD_E12") (pintype "passive"))
      (node (ref "U1") (pin "H1") (pinfunction "VSSB_H1") (pintype "passive"))
      (node (ref "U1") (pin "L1") (pinfunction "VSSVCO_L1") (pintype "passive"))
      (node (ref "U1") (pin "L2") (pinfunction "VSSS_L2") (pintype "passive"))
      (node (ref "U1") (pin "M1") (pinfunction "RFIOM_M1") (pintype "passive"))
      (node (ref "U1") (pin "M3") (pinfunction "RFSUB_M3") (pintype "passive"))
      (node (ref "U2") (pin "10") (pinfunction "EXTI_10") (pintype "passive"))
      (node (ref "U2") (pin "17") (pinfunction "VSSPAD_17") (pintype "passive"))
      (node (ref "U2") (pin "2") (pinfunction "WDI_2") (pintype "passive"))
      (node (ref "U2") (pin "3") (pinfunction "nEXTR_3") (pintype "passive"))
      (node (ref "U2") (pin "9") (pinfunction "VSS_9") (pintype "passive"))
      (node (ref "U3") (pin "4") (pinfunction "VSS_4") (pintype "passive"))
      (node (ref "U3") (pin "9") (pinfunction "EP_9") (pintype "passive"))
      (node (ref "U4") (pin "4") (pinfunction "VSS_4") (pintype "power_in"))
      (node (ref "U5") (pin "11") (pinfunction "GND_11") (pintype "passive"))
      (node (ref "U5") (pin "15") (pinfunction "GND_15") (pintype "passive"))
      (node (ref "U5") (pin "17") (pinfunction "EP_17") (pintype "passive"))
      (node (ref "U5") (pin "3") (pinfunction "GND_3") (pintype "passive"))
      (node (ref "U6") (pin "1") (pinfunction "GND_1") (pintype "passive"))
      (node (ref "U7") (pin "1") (pinfunction "GND_1") (pintype "passive"))
      (node (ref "U8") (pin "1") (pinfunction "GND_1") (pintype "passive"))
      (node (ref "X2") (pin "2") (pinfunction "GND_2") (pintype "passive"))
      (node (ref "X2") (pin "4") (pinfunction "GND_4") (pintype "passive"))
    )
    (net (code "72") (name "Net-(C20-Pad1)") (class "Default")
      (node (ref "C20") (pin "1") (pinfunction "1_1") (pintype "passive"))
      (node (ref "L3") (pin "1") (pinfunction "1_1") (pintype "passive"))
      (node (ref "L4") (pin "2") (pinfunction "2_2") (pintype "passive"))
    )
    (net (code "73") (name "Net-(C43-Pad1)") (class "Default")
      (node (ref "C43") (pin "1") (pinfunction "1_1") (pintype "passive"))
      (node (ref "L4") (pin "1") (pinfunction "1_1") (pintype "passive"))
      (node (ref "R44") (pin "2") (pinfunction "2_2") (pintype "passive"))
    )
    (net (code "74") (name "Net-(C44-Pad1)") (class "Default")
      (node (ref "C44") (pin "1") (pinfunction "1_1") (pintype "passive"))
      (node (ref "D3") (pin "2") (pinfunction "2_2") (pintype "passive"))
      (node (ref "R44") (pin "1") (pinfunction "1_1") (pintype "passive"))
      (node (ref "RF1") (pin "1") (pinfunction "1_1") (pintype "passive"))
    )
    (net (code "75") (name "Net-(C45-Pad1)") (class "Default")
      (node (ref "C45") (pin "1") (pinfunction "1_1") (pintype "passive"))
      (node (ref "R45") (pin "2") (pinfunction "2_2") (pintype "passive"))
    )
    (net (code "76") (name "Net-(D2-A)") (class "Default")
      (node (ref "D2") (pin "2") (pinfunction "A_2") (pintype "passive"))
      (node (ref "J1") (pin "2") (pinfunction "2_2") (pintype "passive"))
      (node (ref "Q1") (pin "3") (pinfunction "D_3") (pintype "passive"))
    )
    (net (code "77") (name "Net-(Q1-G)") (class "Default")
      (node (ref "Q1") (pin "1") (pinfunction "G_1") (pintype "passive"))
      (node (ref "R8") (pin "1") (pinfunction "1_1") (pintype "passive"))
      (node (ref "R9") (pin "1") (pinfunction "1_1") (pintype "passive"))
    )
    (net (code "78") (name "Net-(Q2-B)") (class "Default")
      (node (ref "Q2") (pin "1") (pinfunction "B_1") (pintype "passive"))
      (node (ref "R17") (pin "2") (pinfunction "2_2") (pintype "passive"))
    )
    (net (code "79") (name "Net-(Q2-C)") (class "Default")
      (node (ref "Q2") (pin "3") (pinfunction "C_3") (pintype "passive"))
      (node (ref "R18") (pin "1") (pinfunction "1_1") (pintype "passive"))
    )
    (net (code "80") (name "Net-(TP1-text)") (class "Default")
      (node (ref "TP1") (pin "1") (pinfunction "text_1") (pintype "passive"))
      (node (ref "U1") (pin "E9") (pinfunction "GPIO41_E9") (pintype "passive"))
    )
    (net (code "81") (name "Net-(TP2-text)") (class "Default")
      (node (ref "TP2") (pin "1") (pinfunction "text_1") (pintype "passive"))
      (node (ref "U2") (pin "8") (pinfunction "CLKOUT/nIRQ3_8") (pintype "passive"))
    )
    (net (code "82") (name "Net-(U1A-GPIO17)") (class "Default")
      (node (ref "R2") (pin "2") (pinfunction "2_2") (pintype "passive"))
      (node (ref "U1") (pin "D4") (pinfunction "GPIO17_D4") (pintype "passive"))
    )
    (net (code "83") (name "Net-(U1B-RFIOP)") (class "Default")
      (node (ref "C19") (pin "1") (pinfunction "1_1") (pintype "passive"))
      (node (ref "L3") (pin "2") (pinfunction "2_2") (pintype "passive"))
      (node (ref "U1") (pin "M2") (pinfunction "RFIOP_M2") (pintype "passive"))
    )
    (net (code "84") (name "Net-(U1B-SIMOBUCK_SW)") (class "Default")
      (node (ref "L1") (pin "1") (pinfunction "1_1") (pintype "passive"))
      (node (ref "U1") (pin "A1") (pinfunction "SIMOBUCK_SW_A1") (pintype "passive"))
    )
    (net (code "85") (name "Net-(U1B-SIMOBUCK_SWSEL)") (class "Default")
      (node (ref "L1") (pin "2") (pinfunction "2_2") (pintype "passive"))
      (node (ref "U1") (pin "A2") (pinfunction "SIMOBUCK_SWSEL_A2") (pintype "passive"))
    )
    (net (code "86") (name "Net-(U1B-VDDBH)") (class "Default")
      (node (ref "C14") (pin "1") (pinfunction "1_1") (pintype "passive"))
      (node (ref "L2") (pin "2") (pinfunction "2_2") (pintype "passive"))
      (node (ref "R1") (pin "2") (pinfunction "2_2") (pintype "passive"))
      (node (ref "U1") (pin "G12") (pinfunction "VDDBH_G12") (pintype "passive"))
    )
    (net (code "87") (name "Net-(U1B-VDDBH_RF)") (class "Default")
      (node (ref "C13") (pin "1") (pinfunction "1_1") (pintype "passive"))
      (node (ref "R1") (pin "1") (pinfunction "1_1") (pintype "passive"))
      (node (ref "U1") (pin "J1") (pinfunction "VDDBH_RF_J1") (pintype "passive"))
    )
    (net (code "88") (name "Net-(U1B-VDDBH_SW)") (class "Default")
      (node (ref "L2") (pin "1") (pinfunction "1_1") (pintype "passive"))
      (node (ref "U1") (pin "H12") (pinfunction "VDDBH_SW_H12") (pintype "passive"))
    )
    (net (code "89") (name "Net-(U1B-VDDC)") (class "Default")
      (node (ref "C7") (pin "2") (pinfunction "2_2") (pintype "passive"))
      (node (ref "U1") (pin "A3") (pinfunction "VDDC_A3") (pintype "passive"))
    )
    (net (code "90") (name "Net-(U1B-VDDC_LV)") (class "Default")
      (node (ref "C8") (pin "2") (pinfunction "2_2") (pintype "passive"))
      (node (ref "U1") (pin "B3") (pinfunction "VDDC_LV_B3") (pintype "passive"))
    )
    (net (code "91") (name "Net-(U1B-VDDS)") (class "Default")
      (node (ref "C10") (pin "2") (pinfunction "2_2") (pintype "passive"))
      (node (ref "U1") (pin "C1") (pinfunction "VDDS_C1") (pintype "passive"))
    )
    (net (code "92") (name "Net-(U1B-XI)") (class "Default")
      (node (ref "C16") (pin "1") (pinfunction "1_1") (pintype "passive"))
      (node (ref "U1") (pin "A4") (pinfunction "XI_A4") (pintype "passive"))
      (node (ref "X1") (pin "2") (pinfunction "OSC2_2") (pintype "passive"))
    )
    (net (code "93") (name "Net-(U1B-XI32M)") (class "Default")
      (node (ref "C18") (pin "1") (pinfunction "1_1") (pintype "passive"))
      (node (ref "U1") (pin "C12") (pinfunction "XI32M_C12") (pintype "passive"))
      (node (ref "X2") (pin "1") (pinfunction "1_1") (pintype "passive"))
    )
    (net (code "94") (name "Net-(U1B-XO)") (class "Default")
      (node (ref "C15") (pin "1") (pinfunction "1_1") (pintype "passive"))
      (node (ref "U1") (pin "A5") (pinfunction "XO_A5") (pintype "passive"))
      (node (ref "X1") (pin "1") (pinfunction "OSC1_1") (pintype "passive"))
    )
    (net (code "95") (name "Net-(U1B-XO32M)") (class "Default")
      (node (ref "C17") (pin "2") (pinfunction "2_2") (pintype "passive"))
      (node (ref "U1") (pin "D12") (pinfunction "XO32M_D12") (pintype "passive"))
      (node (ref "X2") (pin "3") (pinfunction "3_3") (pintype "passive"))
    )
    (net (code "96") (name "Net-(U2-AF)") (class "Default")
      (node (ref "C46") (pin "1") (pinfunction "1_1") (pintype "passive"))
      (node (ref "U2") (pin "14") (pinfunction "AF_14") (pintype "passive"))
    )
    (net (code "97") (name "Net-(U2-VBAT)") (class "Default")
      (node (ref "R45") (pin "1") (pinfunction "1_1") (pintype "passive"))
      (node (ref "U2") (pin "5") (pinfunction "VBAT_5") (pintype "passive"))
    )
    (net (code "98") (name "Net-(U2-XI)") (class "Default")
      (node (ref "C50") (pin "1") (pinfunction "1_1") (pintype "passive"))
      (node (ref "U2") (pin "16") (pinfunction "XI_16") (pintype "passive"))
      (node (ref "X3") (pin "2") (pinfunction "OSC2_2") (pintype "passive"))
    )
    (net (code "99") (name "Net-(U2-XO)") (class "Default")
      (node (ref "C51") (pin "1") (pinfunction "1_1") (pintype "passive"))
      (node (ref "U2") (pin "15") (pinfunction "XO_15") (pintype "passive"))
      (node (ref "X3") (pin "1") (pinfunction "OSC1_1") (pintype "passive"))
    )
    (net (code "100") (name "Net-(U4-EXP)") (class "Default")
      (node (ref "R26") (pin "2") (pinfunction "2_2") (pintype "passive"))
      (node (ref "U4") (pin "9") (pinfunction "EXP_9") (pintype "passive"))
    )
    (net (code "101") (name "Net-(U5-BCLK)") (class "Default")
      (node (ref "R14") (pin "2") (pinfunction "2_2") (pintype "passive"))
      (node (ref "U5") (pin "16") (pinfunction "BCLK_16") (pintype "passive"))
    )
    (net (code "102") (name "Net-(U5-DIN)") (class "Default")
      (node (ref "R11") (pin "1") (pinfunction "1_1") (pintype "passive"))
      (node (ref "U5") (pin "1") (pinfunction "DIN_1") (pintype "passive"))
    )
    (net (code "103") (name "Net-(U5-GAIN_SLOT)") (class "Default")
      (node (ref "R12") (pin "1") (pinfunction "1_1") (pintype "passive"))
      (node (ref "U5") (pin "2") (pinfunction "GAIN_SLOT_2") (pintype "passive"))
    )
    (net (code "104") (name "Net-(U5-OUTN)") (class "Default")
      (node (ref "L6") (pin "1") (pinfunction "1_1") (pintype "passive"))
      (node (ref "U5") (pin "10") (pinfunction "OUTN_10") (pintype "passive"))
    )
    (net (code "105") (name "Net-(U5-OUTP)") (class "Default")
      (node (ref "L5") (pin "1") (pinfunction "1_1") (pintype "passive"))
      (node (ref "U5") (pin "9") (pinfunction "OUTP_9") (pintype "passive"))
    )
    (net (code "106") (name "Net-(U6-EN)") (class "Default")
      (node (ref "R47") (pin "1") (pinfunction "1_1") (pintype "passive"))
      (node (ref "U6") (pin "7") (pinfunction "VREF2_7") (pintype "passive"))
      (node (ref "U6") (pin "8") (pinfunction "EN_8") (pintype "passive"))
    )
    (net (code "107") (name "Net-(U7-EN)") (class "Default")
      (node (ref "R58") (pin "1") (pinfunction "1_1") (pintype "passive"))
      (node (ref "U7") (pin "7") (pinfunction "VREF2_7") (pintype "passive"))
      (node (ref "U7") (pin "8") (pinfunction "EN_8") (pintype "passive"))
    )
    (net (code "108") (name "Net-(U8-EN)") (class "Default")
      (node (ref "R59") (pin "1") (pinfunction "1_1") (pintype "passive"))
      (node (ref "U8") (pin "7") (pinfunction "VREF2_7") (pintype "passive"))
      (node (ref "U8") (pin "8") (pinfunction "EN_8") (pintype "passive"))
    )
    (net (code "109") (name "SW1_VDD1V8") (class "Default")
      (node (ref "C35") (pin "1") (pinfunction "1_1") (pintype "passive"))
      (node (ref "FPC1") (pin "4") (pinfunction "4_4") (pintype "passive"))
      (node (ref "J2") (pin "8") (pinfunction "8_8") (pintype "passive"))
      (node (ref "J8") (pin "13") (pinfunction "13_13") (pintype "passive"))
      (node (ref "J8") (pin "14") (pinfunction "14_14") (pintype "passive"))
      (node (ref "J8") (pin "16") (pinfunction "16_16") (pintype "passive"))
    )
    (net (code "110") (name "SW2_VDD1V9") (class "Default")
      (node (ref "C1") (pin "2") (pinfunction "2_2") (pintype "passive"))
      (node (ref "C11") (pin "2") (pinfunction "2_2") (pintype "passive"))
      (node (ref "C12") (pin "1") (pinfunction "1_1") (pintype "passive"))
      (node (ref "C2") (pin "2") (pinfunction "2_2") (pintype "passive"))
      (node (ref "C26") (pin "1") (pinfunction "1_1") (pintype "passive"))
      (node (ref "C27") (pin "1") (pinfunction "1_1") (pintype "passive"))
      (node (ref "C3") (pin "2") (pinfunction "2_2") (pintype "passive"))
      (node (ref "C4") (pin "2") (pinfunction "2_2") (pintype "passive"))
      (node (ref "C41") (pin "1") (pinfunction "1_1") (pintype "passive"))
      (node (ref "C42") (pin "1") (pinfunction "1_1") (pintype "passive"))
      (node (ref "C47") (pin "2") (pinfunction "2_2") (pintype "passive"))
      (node (ref "C49") (pin "1") (pinfunction "1_1") (pintype "passive"))
      (node (ref "C6") (pin "2") (pinfunction "2_2") (pintype "passive"))
      (node (ref "J2") (pin "6") (pinfunction "6_6") (pintype "passive"))
      (node (ref "J7") (pin "4") (pinfunction "4_4") (pintype "passive"))
      (node (ref "J9") (pin "6") (pinfunction "6_6") (pintype "passive"))
      (node (ref "J9") (pin "7") (pinfunction "7_7") (pintype "passive"))
      (node (ref "Q3") (pin "1") (pinfunction "G_1") (pintype "passive"))
      (node (ref "R10") (pin "2") (pinfunction "2_2") (pintype "passive"))
      (node (ref "R20") (pin "2") (pinfunction "2_2") (pintype "passive"))
      (node (ref "R21") (pin "2") (pinfunction "2_2") (pintype "passive"))
      (node (ref "R22") (pin "2") (pinfunction "2_2") (pintype "passive"))
      (node (ref "R23") (pin "2") (pinfunction "2_2") (pintype "passive"))
      (node (ref "R24") (pin "2") (pinfunction "2_2") (pintype "passive"))
      (node (ref "R25") (pin "2") (pinfunction "2_2") (pintype "passive"))
      (node (ref "R27") (pin "1") (pinfunction "1_1") (pintype "passive"))
      (node (ref "R28") (pin "2") (pinfunction "2_2") (pintype "passive"))
      (node (ref "R29") (pin "2") (pinfunction "2_2") (pintype "passive"))
      (node (ref "R3") (pin "2") (pinfunction "2_2") (pintype "passive"))
      (node (ref "R30") (pin "2") (pinfunction "2_2") (pintype "passive"))
      (node (ref "R31") (pin "2") (pinfunction "2_2") (pintype "passive"))
      (node (ref "R46") (pin "2") (pinfunction "2_2") (pintype "passive"))
      (node (ref "R5") (pin "1") (pinfunction "1_1") (pintype "passive"))
      (node (ref "R54") (pin "1") (pinfunction "1_1") (pintype "passive"))
      (node (ref "R55") (pin "1") (pinfunction "1_1") (pintype "passive"))
      (node (ref "R56") (pin "1") (pinfunction "1_1") (pintype "passive"))
      (node (ref "R57") (pin "1") (pinfunction "1_1") (pintype "passive"))
      (node (ref "R61") (pin "1") (pinfunction "1_1") (pintype "passive"))
      (node (ref "R7") (pin "1") (pinfunction "1_1") (pintype "passive"))
      (node (ref "U1") (pin "B1") (pinfunction "VDDP_B1") (pintype "power_in"))
      (node (ref "U1") (pin "C4") (pinfunction "VDDA_C4") (pintype "passive"))
      (node (ref "U1") (pin "E11") (pinfunction "VDDAUDD_E11") (pintype "passive"))
      (node (ref "U1") (pin "G1") (pinfunction "VDDB_G1") (pintype "passive"))
      (node (ref "U1") (pin "M10") (pinfunction "VDDH_M10") (pintype "passive"))
      (node (ref "U1") (pin "M9") (pinfunction "VDDH2_M9") (pintype "passive"))
      (node (ref "U2") (pin "13") (pinfunction "VCC_13") (pintype "passive"))
      (node (ref "U3") (pin "8") (pinfunction "VCC_8") (pintype "passive"))
      (node (ref "U4") (pin "8") (pinfunction "VDD_8") (pintype "power_in"))
      (node (ref "U6") (pin "2") (pinfunction "VREF1_2") (pintype "passive"))
      (node (ref "U7") (pin "2") (pinfunction "VREF1_2") (pintype "passive"))
      (node (ref "U8") (pin "2") (pinfunction "VREF1_2") (pintype "passive"))
    )
    (net (code "111") (name "VCC_1V8") (class "Default")
      (node (ref "C5") (pin "2") (pinfunction "2_2") (pintype "passive"))
      (node (ref "J9") (pin "5") (pinfunction "5_5") (pintype "passive"))
      (node (ref "U1") (pin "B11") (pinfunction "VDDAUDA_B11") (pintype "passive"))
    )
    (net (code "112") (name "VCC_3V3") (class "Default")
      (node (ref "C28") (pin "1") (pinfunction "1_1") (pintype "passive"))
      (node (ref "C29") (pin "1") (pinfunction "1_1") (pintype "passive"))
      (node (ref "C32") (pin "1") (pinfunction "1_1") (pintype "passive"))
      (node (ref "C33") (pin "1") (pinfunction "1_1") (pintype "passive"))
      (node (ref "C34") (pin "1") (pinfunction "1_1") (pintype "passive"))
      (node (ref "C48") (pin "2") (pinfunction "2_2") (pintype "passive"))
      (node (ref "D2") (pin "1") (pinfunction "K_1") (pintype "passive"))
      (node (ref "FPC1") (pin "17") (pinfunction "17_17") (pintype "passive"))
      (node (ref "FPC1") (pin "3") (pinfunction "3_3") (pintype "passive"))
      (node (ref "J1") (pin "1") (pinfunction "1_1") (pintype "passive"))
      (node (ref "J3") (pin "8") (pinfunction "8_8") (pintype "passive"))
      (node (ref "J9") (pin "13") (pinfunction "13_13") (pintype "passive"))
      (node (ref "J9") (pin "14") (pinfunction "14_14") (pintype "passive"))
      (node (ref "J9") (pin "16") (pinfunction "16_16") (pintype "passive"))
      (node (ref "R13") (pin "2") (pinfunction "2_2") (pintype "passive"))
      (node (ref "R47") (pin "2") (pinfunction "2_2") (pintype "passive"))
      (node (ref "R48") (pin "1") (pinfunction "1_1") (pintype "passive"))
      (node (ref "R49") (pin "1") (pinfunction "1_1") (pintype "passive"))
      (node (ref "R50") (pin "1") (pinfunction "1_1") (pintype "passive"))
      (node (ref "R51") (pin "1") (pinfunction "1_1") (pintype "passive"))
      (node (ref "R52") (pin "1") (pinfunction "1_1") (pintype "passive"))
      (node (ref "R53") (pin "1") (pinfunction "1_1") (pintype "passive"))
      (node (ref "R58") (pin "2") (pinfunction "2_2") (pintype "passive"))
      (node (ref "R59") (pin "2") (pinfunction "2_2") (pintype "passive"))
      (node (ref "U5") (pin "7") (pinfunction "VDD_7") (pintype "passive"))
      (node (ref "U5") (pin "8") (pinfunction "VDD_8") (pintype "passive"))
    )
    (net (code "113") (name "unconnected-(U1A-GPIO02-PadK4)") (class "Default")
      (node (ref "U1") (pin "K4") (pinfunction "GPIO02_K4") (pintype "passive+no_connect"))
    )
    (net (code "114") (name "unconnected-(U1A-GPIO10-PadE6)") (class "Default")
      (node (ref "U1") (pin "E6") (pinfunction "GPIO10_E6") (pintype "passive+no_connect"))
    )
    (net (code "115") (name "unconnected-(U1A-GPIO11-PadE4)") (class "Default")
      (node (ref "U1") (pin "E4") (pinfunction "GPIO11_E4") (pintype "passive+no_connect"))
    )
    (net (code "116") (name "unconnected-(U1A-GPIO16-PadD7)") (class "Default")
      (node (ref "U1") (pin "D7") (pinfunction "GPIO16_D7") (pintype "passive+no_connect"))
    )
    (net (code "117") (name "unconnected-(U1A-GPIO24-PadE2)") (class "Default")
      (node (ref "U1") (pin "E2") (pinfunction "GPIO24_E2") (pintype "passive+no_connect"))
    )
    (net (code "118") (name "unconnected-(U1A-GPIO27-PadM5)") (class "Default")
      (node (ref "U1") (pin "M5") (pinfunction "GPIO27_M5") (pintype "passive+no_connect"))
    )
    (net (code "119") (name "unconnected-(U1A-GPIO33-PadG3)") (class "Default")
      (node (ref "U1") (pin "G3") (pinfunction "GPIO33_G3") (pintype "passive+no_connect"))
    )
    (net (code "120") (name "unconnected-(U1A-GPIO39-PadC9)") (class "Default")
      (node (ref "U1") (pin "C9") (pinfunction "GPIO39_C9") (pintype "passive+no_connect"))
    )
    (net (code "121") (name "unconnected-(U1A-GPIO40-PadC10)") (class "Default")
      (node (ref "U1") (pin "C10") (pinfunction "GPIO40_C10") (pintype "passive+no_connect"))
    )
    (net (code "122") (name "unconnected-(U1A-GPIO43-PadD10)") (class "Default")
      (node (ref "U1") (pin "D10") (pinfunction "GPIO43_D10") (pintype "passive+no_connect"))
    )
    (net (code "123") (name "unconnected-(U1A-GPIO45-PadF10)") (class "Default")
      (node (ref "U1") (pin "F10") (pinfunction "GPIO45_F10") (pintype "passive+no_connect"))
    )
    (net (code "124") (name "unconnected-(U1A-GPIO49-PadD1)") (class "Default")
      (node (ref "U1") (pin "D1") (pinfunction "GPIO49_D1") (pintype "passive+no_connect"))
    )
    (net (code "125") (name "unconnected-(U1A-GPIO63-PadM6)") (class "Default")
      (node (ref "U1") (pin "M6") (pinfunction "GPIO63_M6") (pintype "passive+no_connect"))
    )
    (net (code "126") (name "unconnected-(U1A-GPIO86-PadG10)") (class "Default")
      (node (ref "U1") (pin "G10") (pinfunction "GPIO86_G10") (pintype "passive+no_connect"))
    )
    (net (code "127") (name "unconnected-(U1A-GPIO87-PadG9)") (class "Default")
      (node (ref "U1") (pin "G9") (pinfunction "GPIO87_G9") (pintype "passive+no_connect"))
    )
    (net (code "128") (name "unconnected-(U1A-GPIO88-PadF9)") (class "Default")
      (node (ref "U1") (pin "F9") (pinfunction "GPIO88_F9") (pintype "passive+no_connect"))
    )
    (net (code "129") (name "unconnected-(U1A-GPIO93-PadM4)") (class "Default")
      (node (ref "U1") (pin "M4") (pinfunction "GPIO93_M4") (pintype "passive+no_connect"))
    )
    (net (code "130") (name "unconnected-(U1B-NC-PadA10)") (class "Default")
      (node (ref "U1") (pin "A10") (pinfunction "NC_A10") (pintype "passive+no_connect"))
    )
    (net (code "131") (name "unconnected-(U1B-NC-PadA11)") (class "Default")
      (node (ref "U1") (pin "A11") (pinfunction "NC_A11") (pintype "passive+no_connect"))
    )
    (net (code "132") (name "unconnected-(U1B-NC-PadA12)") (class "Default")
      (node (ref "U1") (pin "A12") (pinfunction "NC_A12") (pintype "passive+no_connect"))
    )
    (net (code "133") (name "unconnected-(U1B-NC-PadB10)") (class "Default")
      (node (ref "U1") (pin "B10") (pinfunction "NC_B10") (pintype "passive+no_connect"))
    )
    (net (code "134") (name "unconnected-(U1B-NC-PadC11)") (class "Default")
      (node (ref "U1") (pin "C11") (pinfunction "NC_C11") (pintype "passive+no_connect"))
    )
    (net (code "135") (name "unconnected-(U1B-NC-PadD11)") (class "Default")
      (node (ref "U1") (pin "D11") (pinfunction "NC_D11") (pintype "passive+no_connect"))
    )
    (net (code "136") (name "unconnected-(U1B-NC-PadE3)") (class "Default")
      (node (ref "U1") (pin "E3") (pinfunction "NC_E3") (pintype "passive+no_connect"))
    )
    (net (code "137") (name "unconnected-(U1B-NC-PadF4)") (class "Default")
      (node (ref "U1") (pin "F4") (pinfunction "NC_F4") (pintype "passive+no_connect"))
    )
    (net (code "138") (name "unconnected-(U1B-NC-PadG4)") (class "Default")
      (node (ref "U1") (pin "G4") (pinfunction "NC_G4") (pintype "passive+no_connect"))
    )
    (net (code "139") (name "unconnected-(U1B-NC-PadH10)") (class "Default")
      (node (ref "U1") (pin "H10") (pinfunction "NC_H10") (pintype "passive+no_connect"))
    )
    (net (code "140") (name "unconnected-(U1B-NC-PadJ7)") (class "Default")
      (node (ref "U1") (pin "J7") (pinfunction "NC_J7") (pintype "passive+no_connect"))
    )
    (net (code "141") (name "unconnected-(U1B-NC-PadJ8)") (class "Default")
      (node (ref "U1") (pin "J8") (pinfunction "NC_J8") (pintype "passive+no_connect"))
    )
    (net (code "142") (name "unconnected-(U1B-NC-PadJ10)") (class "Default")
      (node (ref "U1") (pin "J10") (pinfunction "NC_J10") (pintype "passive+no_connect"))
    )
    (net (code "143") (name "unconnected-(U1B-NC-PadJ12)") (class "Default")
      (node (ref "U1") (pin "J12") (pinfunction "NC_J12") (pintype "passive+no_connect"))
    )
    (net (code "144") (name "unconnected-(U1B-NC-PadK7)") (class "Default")
      (node (ref "U1") (pin "K7") (pinfunction "NC_K7") (pintype "passive+no_connect"))
    )
    (net (code "145") (name "unconnected-(U1B-NC-PadK8)") (class "Default")
      (node (ref "U1") (pin "K8") (pinfunction "NC_K8") (pintype "passive+no_connect"))
    )
    (net (code "146") (name "unconnected-(U1B-NC-PadK12)") (class "Default")
      (node (ref "U1") (pin "K12") (pinfunction "NC_K12") (pintype "passive+no_connect"))
    )
    (net (code "147") (name "unconnected-(U1B-NC-PadL7)") (class "Default")
      (node (ref "U1") (pin "L7") (pinfunction "NC_L7") (pintype "passive+no_connect"))
    )
    (net (code "148") (name "unconnected-(U1B-NC-PadL8)") (class "Default")
      (node (ref "U1") (pin "L8") (pinfunction "NC_L8") (pintype "passive+no_connect"))
    )
    (net (code "149") (name "unconnected-(U1B-NC-PadL12)") (class "Default")
      (node (ref "U1") (pin "L12") (pinfunction "NC_L12") (pintype "passive+no_connect"))
    )
    (net (code "150") (name "unconnected-(U1B-NC-PadM7)") (class "Default")
      (node (ref "U1") (pin "M7") (pinfunction "NC_M7") (pintype "passive+no_connect"))
    )
    (net (code "151") (name "unconnected-(U1B-NC-PadM8)") (class "Default")
      (node (ref "U1") (pin "M8") (pinfunction "NC_M8") (pintype "passive+no_connect"))
    )
    (net (code "152") (name "unconnected-(U1B-NC-PadM12)") (class "Default")
      (node (ref "U1") (pin "M12") (pinfunction "NC_M12") (pintype "passive+no_connect"))
    )
    (net (code "153") (name "unconnected-(U1B-TXEN-PadK1)") (class "Default")
      (node (ref "U1") (pin "K1") (pinfunction "TXEN_K1") (pintype "passive+no_connect"))
    )
    (net (code "154") (name "unconnected-(U2-PSW{slash}nIRQ2-Pad4)") (class "Default")
      (node (ref "U2") (pin "4") (pinfunction "PSW/nIRQ2_4") (pintype "passive+no_connect"))
    )
    (net (code "155") (name "unconnected-(U2-nRST-Pad1)") (class "Default")
      (node (ref "U2") (pin "1") (pinfunction "nRST_1") (pintype "passive+no_connect"))
    )
    (net (code "156") (name "unconnected-(U2-nTIRQ-Pad12)") (class "Default")
      (node (ref "U2") (pin "12") (pinfunction "nTIRQ_12") (pintype "passive+no_connect"))
    )
    (net (code "157") (name "unconnected-(U5-N.C.-Pad5)") (class "Default")
      (node (ref "U5") (pin "5") (pinfunction "N.C._5") (pintype "passive+no_connect"))
    )
    (net (code "158") (name "unconnected-(U5-N.C.-Pad6)") (class "Default")
      (node (ref "U5") (pin "6") (pinfunction "N.C._6") (pintype "passive+no_connect"))
    )
    (net (code "159") (name "unconnected-(U5-N.C.-Pad12)") (class "Default")
      (node (ref "U5") (pin "12") (pinfunction "N.C._12") (pintype "passive+no_connect"))
    )
    (net (code "160") (name "unconnected-(U5-N.C.-Pad13)") (class "Default")
      (node (ref "U5") (pin "13") (pinfunction "N.C._13") (pintype "passive+no_connect"))
    )
  )
)
